# homeboard20.net
KiCad netlist of a schematic drawn in EAGLE
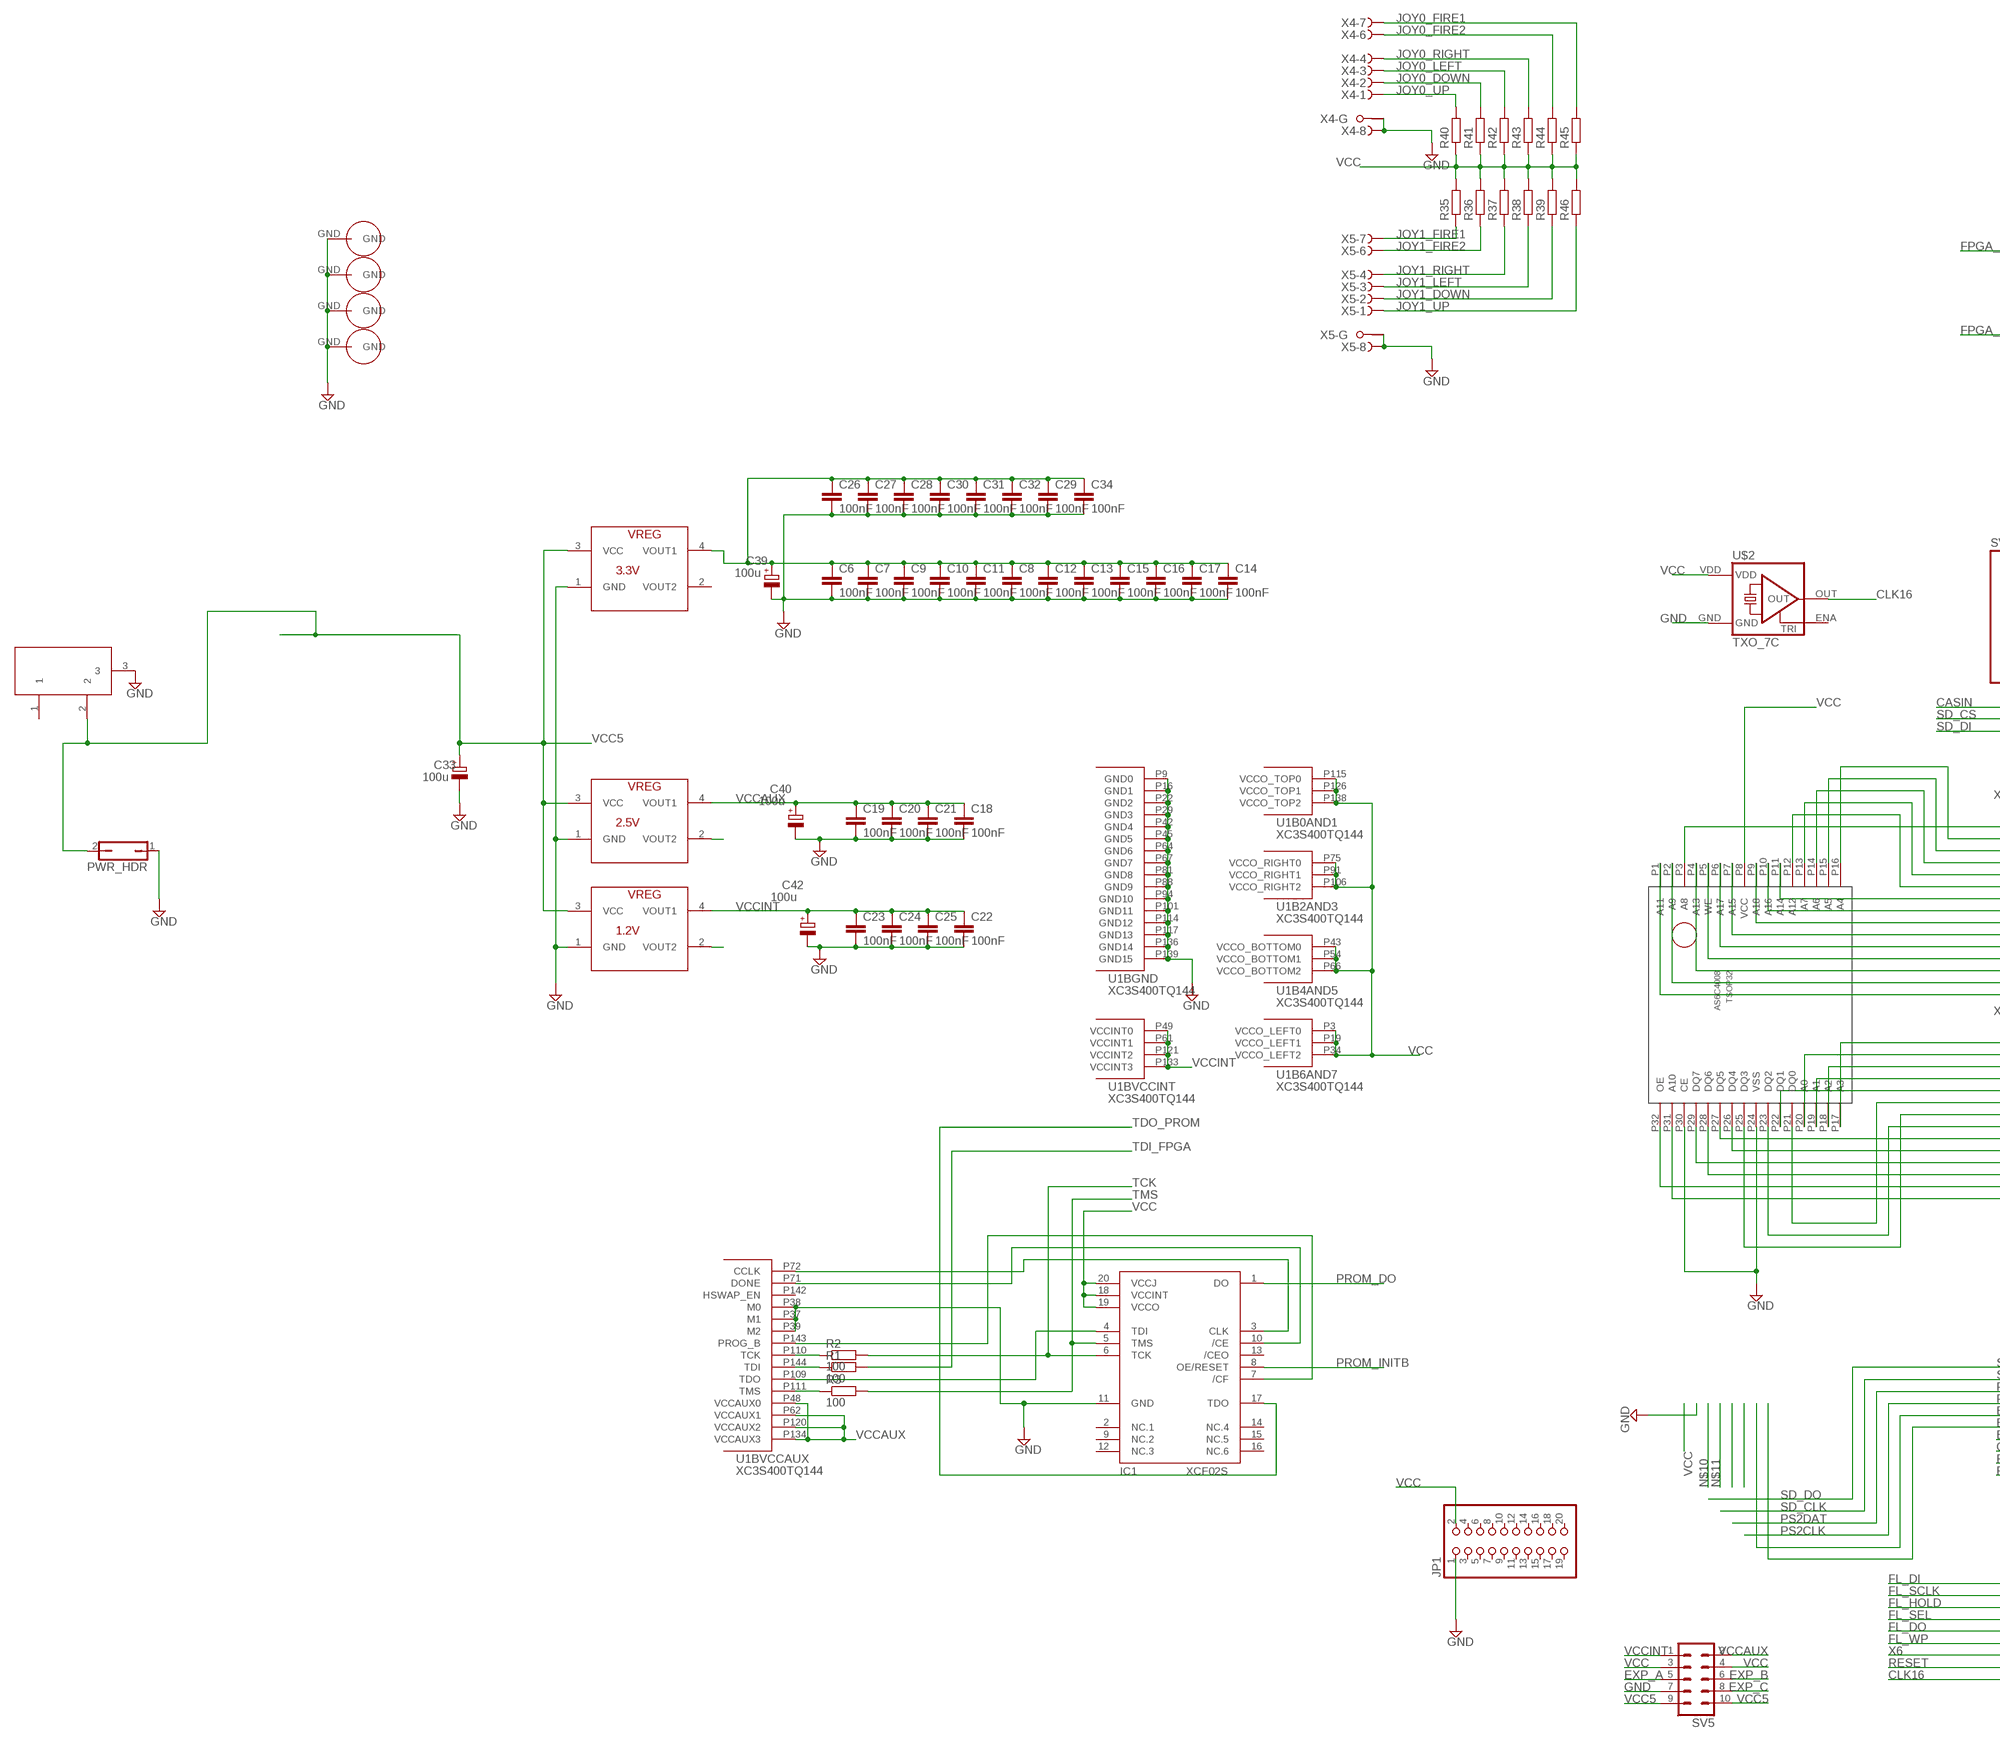
[diagram p0: schematic, sheet 1, part 1 of 3]
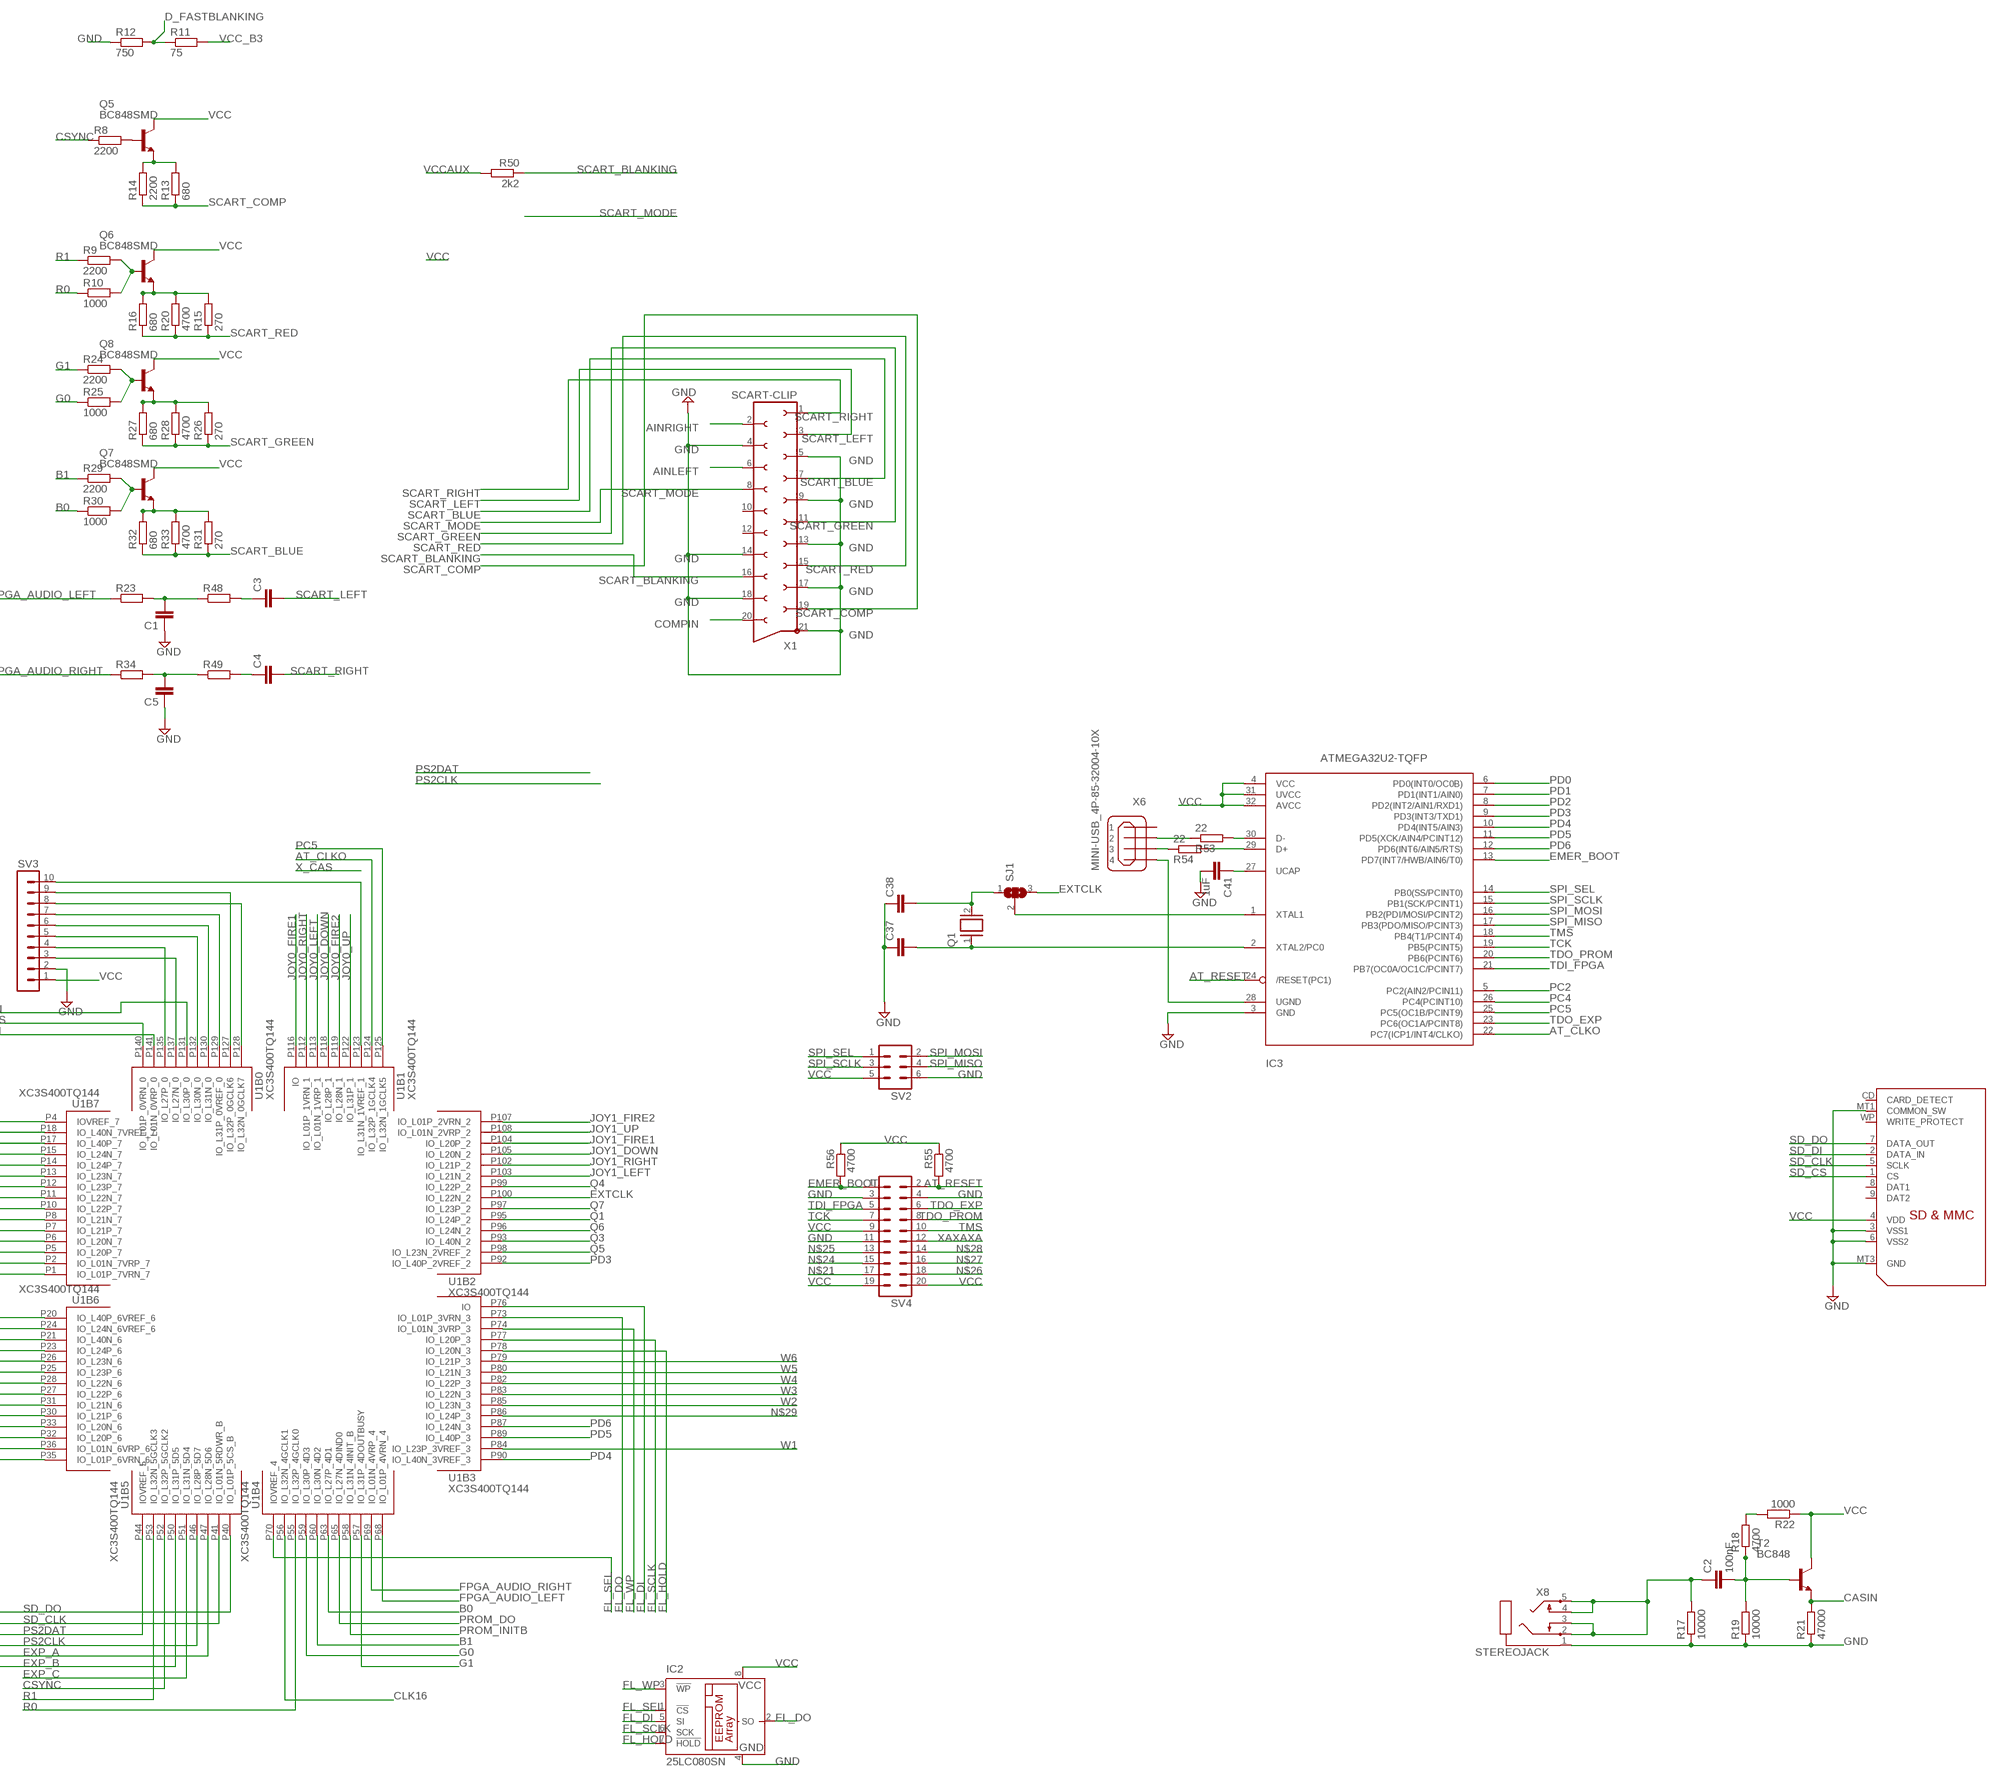
[diagram p1: schematic, sheet 1, part 2 of 3]
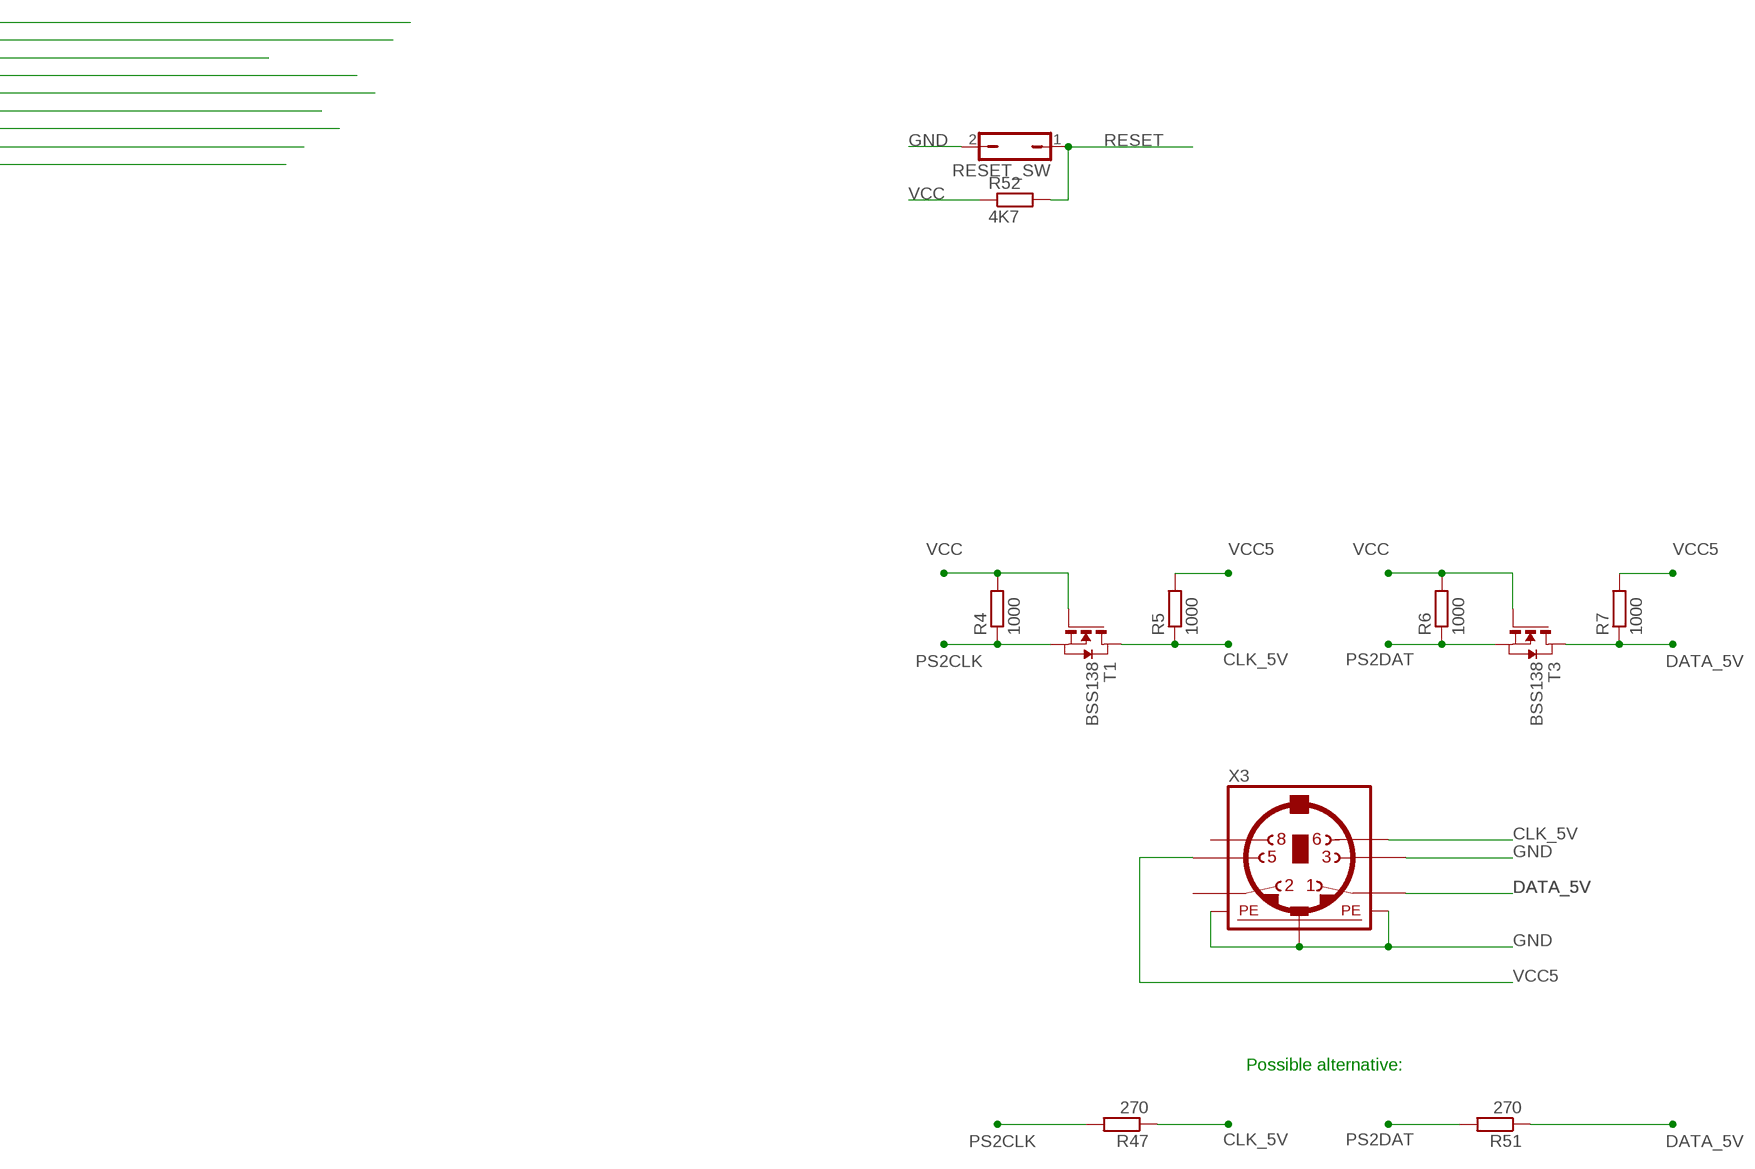
[diagram p2: schematic, sheet 1, part 3 of 3]

(export (version "E")
  (design (tool "Eeschema 10.0.6"))
  (components
    (comp (ref "C1")
      (value "C-EUC0603")
      (footprint "eagle-import:C0603")
      (libsource (lib "eagle-import") (part "resistor_C-EUC0603"))
    )
    (comp (ref "C2")
      (value "100nF")
      (footprint "eagle-import:C0603")
      (libsource (lib "eagle-import") (part "resistor_C-EUC0603"))
    )
    (comp (ref "C3")
      (value "C-EUC0603")
      (footprint "eagle-import:C0603")
      (libsource (lib "eagle-import") (part "resistor_C-EUC0603"))
    )
    (comp (ref "C4")
      (value "C-EUC0603")
      (footprint "eagle-import:C0603")
      (libsource (lib "eagle-import") (part "resistor_C-EUC0603"))
    )
    (comp (ref "C5")
      (value "C-EUC0603")
      (footprint "eagle-import:C0603")
      (libsource (lib "eagle-import") (part "resistor_C-EUC0603"))
    )
    (comp (ref "C6")
      (value "100nF")
      (footprint "eagle-import:C0603")
      (libsource (lib "eagle-import") (part "C-EUC0603"))
    )
    (comp (ref "C7")
      (value "100nF")
      (footprint "eagle-import:C0603")
      (libsource (lib "eagle-import") (part "C-EUC0603"))
    )
    (comp (ref "C8")
      (value "100nF")
      (footprint "eagle-import:C0603")
      (libsource (lib "eagle-import") (part "C-EUC0603"))
    )
    (comp (ref "C9")
      (value "100nF")
      (footprint "eagle-import:C0603")
      (libsource (lib "eagle-import") (part "C-EUC0603"))
    )
    (comp (ref "C10")
      (value "100nF")
      (footprint "eagle-import:C0603")
      (libsource (lib "eagle-import") (part "C-EUC0603"))
    )
    (comp (ref "C11")
      (value "100nF")
      (footprint "eagle-import:C0603")
      (libsource (lib "eagle-import") (part "C-EUC0603"))
    )
    (comp (ref "C12")
      (value "100nF")
      (footprint "eagle-import:C0603")
      (libsource (lib "eagle-import") (part "C-EUC0603"))
    )
    (comp (ref "C13")
      (value "100nF")
      (footprint "eagle-import:C0603")
      (libsource (lib "eagle-import") (part "C-EUC0603"))
    )
    (comp (ref "C14")
      (value "100nF")
      (footprint "eagle-import:C0603")
      (libsource (lib "eagle-import") (part "C-EUC0603"))
    )
    (comp (ref "C15")
      (value "100nF")
      (footprint "eagle-import:C0603")
      (libsource (lib "eagle-import") (part "C-EUC0603"))
    )
    (comp (ref "C16")
      (value "100nF")
      (footprint "eagle-import:C0603")
      (libsource (lib "eagle-import") (part "C-EUC0603"))
    )
    (comp (ref "C17")
      (value "100nF")
      (footprint "eagle-import:C0603")
      (libsource (lib "eagle-import") (part "C-EUC0603"))
    )
    (comp (ref "C18")
      (value "100nF")
      (footprint "eagle-import:C0603")
      (libsource (lib "eagle-import") (part "C-EUC0603"))
    )
    (comp (ref "C19")
      (value "100nF")
      (footprint "eagle-import:C0603")
      (libsource (lib "eagle-import") (part "C-EUC0603"))
    )
    (comp (ref "C20")
      (value "100nF")
      (footprint "eagle-import:C0603")
      (libsource (lib "eagle-import") (part "C-EUC0603"))
    )
    (comp (ref "C21")
      (value "100nF")
      (footprint "eagle-import:C0603")
      (libsource (lib "eagle-import") (part "C-EUC0603"))
    )
    (comp (ref "C22")
      (value "100nF")
      (footprint "eagle-import:C0603")
      (libsource (lib "eagle-import") (part "C-EUC0603"))
    )
    (comp (ref "C23")
      (value "100nF")
      (footprint "eagle-import:C0603")
      (libsource (lib "eagle-import") (part "C-EUC0603"))
    )
    (comp (ref "C24")
      (value "100nF")
      (footprint "eagle-import:C0603")
      (libsource (lib "eagle-import") (part "C-EUC0603"))
    )
    (comp (ref "C25")
      (value "100nF")
      (footprint "eagle-import:C0603")
      (libsource (lib "eagle-import") (part "C-EUC0603"))
    )
    (comp (ref "C26")
      (value "100nF")
      (footprint "eagle-import:C0603")
      (libsource (lib "eagle-import") (part "C-EUC0603"))
    )
    (comp (ref "C27")
      (value "100nF")
      (footprint "eagle-import:C0603")
      (libsource (lib "eagle-import") (part "C-EUC0603"))
    )
    (comp (ref "C28")
      (value "100nF")
      (footprint "eagle-import:C0603")
      (libsource (lib "eagle-import") (part "C-EUC0603"))
    )
    (comp (ref "C29")
      (value "100nF")
      (footprint "eagle-import:C0603")
      (libsource (lib "eagle-import") (part "C-EUC0603"))
    )
    (comp (ref "C30")
      (value "100nF")
      (footprint "eagle-import:C0603")
      (libsource (lib "eagle-import") (part "C-EUC0603"))
    )
    (comp (ref "C31")
      (value "100nF")
      (footprint "eagle-import:C0603")
      (libsource (lib "eagle-import") (part "C-EUC0603"))
    )
    (comp (ref "C32")
      (value "100nF")
      (footprint "eagle-import:C0603")
      (libsource (lib "eagle-import") (part "C-EUC0603"))
    )
    (comp (ref "C33")
      (value "100u")
      (footprint "eagle-import:PANASONIC_D")
      (libsource (lib "eagle-import") (part "CPOL-EUD"))
    )
    (comp (ref "C34")
      (value "100nF")
      (footprint "eagle-import:C0603")
      (libsource (lib "eagle-import") (part "C-EUC0603"))
    )
    (comp (ref "C37")
      (value "C-EUC0805")
      (footprint "eagle-import:C0805")
      (libsource (lib "eagle-import") (part "C-EUC0805"))
    )
    (comp (ref "C38")
      (value "C-EUC0805")
      (footprint "eagle-import:C0805")
      (libsource (lib "eagle-import") (part "C-EUC0805"))
    )
    (comp (ref "C39")
      (value "100u")
      (footprint "eagle-import:PANASONIC_D")
      (libsource (lib "eagle-import") (part "CPOL-EUD"))
    )
    (comp (ref "C40")
      (value "100u")
      (footprint "eagle-import:PANASONIC_D")
      (libsource (lib "eagle-import") (part "CPOL-EUD"))
    )
    (comp (ref "C41")
      (value "1uF")
      (footprint "eagle-import:C0805")
      (libsource (lib "eagle-import") (part "C-EUC0805"))
    )
    (comp (ref "C42")
      (value "100u")
      (footprint "eagle-import:PANASONIC_D")
      (libsource (lib "eagle-import") (part "CPOL-EUD"))
    )
    (comp (ref "IC1")
      (value "XCF02S")
      (footprint "eagle-import:VO20")
      (libsource (lib "eagle-import") (part "XCF02S"))
    )
    (comp (ref "IC2")
      (value "25LC080SN")
      (footprint "eagle-import:SO-08")
      (fields (field (name "MF") "MICROCHIP") (field (name "MPN") "25LC080/SN"))
      (libsource (lib "eagle-import") (part "25SNLC080"))
    )
    (comp (ref "IC3")
      (value "ATMEGA32U2-TQFP")
      (footprint "eagle-import:TQFP32-08")
      (libsource (lib "eagle-import") (part "ATMEGA32U2-TQFP"))
    )
    (comp (ref "JP1")
      (value "PINHD-2X10")
      (footprint "eagle-import:2X10")
      (libsource (lib "eagle-import") (part "PINHD-2X10"))
    )
    (comp (ref "PWR_HDR")
      (value "JP1Q")
      (footprint "eagle-import:JP1")
      (libsource (lib "eagle-import") (part "JP1Q"))
    )
    (comp (ref "Q1")
      (value "XTAL/S")
      (footprint "eagle-import:QS")
      (libsource (lib "eagle-import") (part "XTAL/S"))
    )
    (comp (ref "Q5")
      (value "BC848SMD")
      (footprint "eagle-import:SOT23")
      (libsource (lib "eagle-import") (part "BC848SMD"))
    )
    (comp (ref "Q6")
      (value "BC848SMD")
      (footprint "eagle-import:SOT23")
      (libsource (lib "eagle-import") (part "BC848SMD"))
    )
    (comp (ref "Q7")
      (value "BC848SMD")
      (footprint "eagle-import:SOT23")
      (libsource (lib "eagle-import") (part "BC848SMD"))
    )
    (comp (ref "Q8")
      (value "BC848SMD")
      (footprint "eagle-import:SOT23")
      (libsource (lib "eagle-import") (part "BC848SMD"))
    )
    (comp (ref "R1")
      (value "100")
      (footprint "eagle-import:R0805")
      (libsource (lib "eagle-import") (part "R-EU_R0805"))
    )
    (comp (ref "R2")
      (value "100")
      (footprint "eagle-import:R0805")
      (libsource (lib "eagle-import") (part "R-EU_R0805"))
    )
    (comp (ref "R3")
      (value "100")
      (footprint "eagle-import:R0805")
      (libsource (lib "eagle-import") (part "R-EU_R0805"))
    )
    (comp (ref "R4")
      (value "1000")
      (footprint "eagle-import:R0805")
      (libsource (lib "eagle-import") (part "R-EU_R0805"))
    )
    (comp (ref "R5")
      (value "1000")
      (footprint "eagle-import:R0805")
      (libsource (lib "eagle-import") (part "R-EU_R0805"))
    )
    (comp (ref "R6")
      (value "1000")
      (footprint "eagle-import:R0805")
      (libsource (lib "eagle-import") (part "R-EU_R0805"))
    )
    (comp (ref "R7")
      (value "1000")
      (footprint "eagle-import:R0805")
      (libsource (lib "eagle-import") (part "R-EU_R0805"))
    )
    (comp (ref "R8")
      (value "2200")
      (footprint "eagle-import:R0805")
      (libsource (lib "eagle-import") (part "R-EU_R0805"))
    )
    (comp (ref "R9")
      (value "2200")
      (footprint "eagle-import:R0805")
      (libsource (lib "eagle-import") (part "R-EU_R0805"))
    )
    (comp (ref "R10")
      (value "1000")
      (footprint "eagle-import:R0805")
      (libsource (lib "eagle-import") (part "R-EU_R0805"))
    )
    (comp (ref "R11")
      (value "75")
      (footprint "eagle-import:R0805")
      (libsource (lib "eagle-import") (part "R-EU_R0805"))
    )
    (comp (ref "R12")
      (value "750")
      (footprint "eagle-import:R0805")
      (libsource (lib "eagle-import") (part "R-EU_R0805"))
    )
    (comp (ref "R13")
      (value "680")
      (footprint "eagle-import:R0805")
      (libsource (lib "eagle-import") (part "R-EU_R0805"))
    )
    (comp (ref "R14")
      (value "2200")
      (footprint "eagle-import:R0805")
      (libsource (lib "eagle-import") (part "R-EU_R0805"))
    )
    (comp (ref "R15")
      (value "270")
      (footprint "eagle-import:R0805")
      (libsource (lib "eagle-import") (part "R-EU_R0805"))
    )
    (comp (ref "R16")
      (value "680")
      (footprint "eagle-import:R0805")
      (libsource (lib "eagle-import") (part "R-EU_R0805"))
    )
    (comp (ref "R17")
      (value "10000")
      (footprint "eagle-import:R0805")
      (libsource (lib "eagle-import") (part "R-EU_R0805"))
    )
    (comp (ref "R18")
      (value "4700")
      (footprint "eagle-import:R0805")
      (libsource (lib "eagle-import") (part "R-EU_R0805"))
    )
    (comp (ref "R19")
      (value "10000")
      (footprint "eagle-import:R0805")
      (libsource (lib "eagle-import") (part "R-EU_R0805"))
    )
    (comp (ref "R20")
      (value "4700")
      (footprint "eagle-import:R0805")
      (libsource (lib "eagle-import") (part "R-EU_R0805"))
    )
    (comp (ref "R21")
      (value "47000")
      (footprint "eagle-import:R0805")
      (libsource (lib "eagle-import") (part "R-EU_R0805"))
    )
    (comp (ref "R22")
      (value "1000")
      (footprint "eagle-import:R0805")
      (libsource (lib "eagle-import") (part "R-EU_R0805"))
    )
    (comp (ref "R23")
      (value "R-EU_M0805")
      (footprint "eagle-import:M0805")
      (libsource (lib "eagle-import") (part "resistor_R-EU_M0805"))
    )
    (comp (ref "R24")
      (value "2200")
      (footprint "eagle-import:R0805")
      (libsource (lib "eagle-import") (part "R-EU_R0805"))
    )
    (comp (ref "R25")
      (value "1000")
      (footprint "eagle-import:R0805")
      (libsource (lib "eagle-import") (part "R-EU_R0805"))
    )
    (comp (ref "R26")
      (value "270")
      (footprint "eagle-import:R0805")
      (libsource (lib "eagle-import") (part "R-EU_R0805"))
    )
    (comp (ref "R27")
      (value "680")
      (footprint "eagle-import:R0805")
      (libsource (lib "eagle-import") (part "R-EU_R0805"))
    )
    (comp (ref "R28")
      (value "4700")
      (footprint "eagle-import:R0805")
      (libsource (lib "eagle-import") (part "R-EU_R0805"))
    )
    (comp (ref "R29")
      (value "2200")
      (footprint "eagle-import:R0805")
      (libsource (lib "eagle-import") (part "R-EU_R0805"))
    )
    (comp (ref "R30")
      (value "1000")
      (footprint "eagle-import:R0805")
      (libsource (lib "eagle-import") (part "R-EU_R0805"))
    )
    (comp (ref "R31")
      (value "270")
      (footprint "eagle-import:R0805")
      (libsource (lib "eagle-import") (part "R-EU_R0805"))
    )
    (comp (ref "R32")
      (value "680")
      (footprint "eagle-import:R0805")
      (libsource (lib "eagle-import") (part "R-EU_R0805"))
    )
    (comp (ref "R33")
      (value "4700")
      (footprint "eagle-import:R0805")
      (libsource (lib "eagle-import") (part "R-EU_R0805"))
    )
    (comp (ref "R34")
      (value "R-EU_M0805")
      (footprint "eagle-import:M0805")
      (libsource (lib "eagle-import") (part "resistor_R-EU_M0805"))
    )
    (comp (ref "R35")
      (value "R-EU_M0805")
      (footprint "eagle-import:M0805")
      (libsource (lib "eagle-import") (part "resistor_R-EU_M0805"))
    )
    (comp (ref "R36")
      (value "R-EU_M0805")
      (footprint "eagle-import:M0805")
      (libsource (lib "eagle-import") (part "resistor_R-EU_M0805"))
    )
    (comp (ref "R37")
      (value "R-EU_M0805")
      (footprint "eagle-import:M0805")
      (libsource (lib "eagle-import") (part "resistor_R-EU_M0805"))
    )
    (comp (ref "R38")
      (value "R-EU_M0805")
      (footprint "eagle-import:M0805")
      (libsource (lib "eagle-import") (part "resistor_R-EU_M0805"))
    )
    (comp (ref "R39")
      (value "R-EU_M0805")
      (footprint "eagle-import:M0805")
      (libsource (lib "eagle-import") (part "resistor_R-EU_M0805"))
    )
    (comp (ref "R40")
      (value "R-EU_M0805")
      (footprint "eagle-import:M0805")
      (libsource (lib "eagle-import") (part "resistor_R-EU_M0805"))
    )
    (comp (ref "R41")
      (value "R-EU_M0805")
      (footprint "eagle-import:M0805")
      (libsource (lib "eagle-import") (part "resistor_R-EU_M0805"))
    )
    (comp (ref "R42")
      (value "R-EU_M0805")
      (footprint "eagle-import:M0805")
      (libsource (lib "eagle-import") (part "resistor_R-EU_M0805"))
    )
    (comp (ref "R43")
      (value "R-EU_M0805")
      (footprint "eagle-import:M0805")
      (libsource (lib "eagle-import") (part "resistor_R-EU_M0805"))
    )
    (comp (ref "R44")
      (value "R-EU_M0805")
      (footprint "eagle-import:M0805")
      (libsource (lib "eagle-import") (part "resistor_R-EU_M0805"))
    )
    (comp (ref "R45")
      (value "R-EU_M0805")
      (footprint "eagle-import:M0805")
      (libsource (lib "eagle-import") (part "resistor_R-EU_M0805"))
    )
    (comp (ref "R46")
      (value "R-EU_M0805")
      (footprint "eagle-import:M0805")
      (libsource (lib "eagle-import") (part "resistor_R-EU_M0805"))
    )
    (comp (ref "R47")
      (value "270")
      (footprint "eagle-import:R0805")
      (libsource (lib "eagle-import") (part "R-EU_R0805"))
    )
    (comp (ref "R48")
      (value "R-EU_M0805")
      (footprint "eagle-import:M0805")
      (libsource (lib "eagle-import") (part "resistor_R-EU_M0805"))
    )
    (comp (ref "R49")
      (value "R-EU_M0805")
      (footprint "eagle-import:M0805")
      (libsource (lib "eagle-import") (part "resistor_R-EU_M0805"))
    )
    (comp (ref "R50")
      (value "2k2")
      (footprint "eagle-import:M0805")
      (libsource (lib "eagle-import") (part "resistor_R-EU_M0805"))
    )
    (comp (ref "R51")
      (value "270")
      (footprint "eagle-import:R0805")
      (libsource (lib "eagle-import") (part "R-EU_R0805"))
    )
    (comp (ref "R52")
      (value "4K7")
      (footprint "eagle-import:M0805")
      (libsource (lib "eagle-import") (part "resistor_R-EU_M0805"))
    )
    (comp (ref "R53")
      (value "22")
      (footprint "eagle-import:R0805")
      (libsource (lib "eagle-import") (part "R-EU_R0805"))
    )
    (comp (ref "R54")
      (value "22")
      (footprint "eagle-import:R0805")
      (libsource (lib "eagle-import") (part "R-EU_R0805"))
    )
    (comp (ref "R55")
      (value "4700")
      (footprint "eagle-import:R0805")
      (libsource (lib "eagle-import") (part "R-EU_R0805"))
    )
    (comp (ref "R56")
      (value "4700")
      (footprint "eagle-import:R0805")
      (libsource (lib "eagle-import") (part "R-EU_R0805"))
    )
    (comp (ref "REG1.2")
      (value "1.2V")
      (footprint "eagle-import:SOT223")
      (libsource (lib "eagle-import") (part "NX1117"))
    )
    (comp (ref "REG2.5")
      (value "2.5V")
      (footprint "eagle-import:SOT223")
      (libsource (lib "eagle-import") (part "NX1117"))
    )
    (comp (ref "RESET_SW")
      (value "JP1Q")
      (footprint "eagle-import:JP1")
      (libsource (lib "eagle-import") (part "JP1Q"))
    )
    (comp (ref "SJ1")
      (value "SJ2W")
      (footprint "eagle-import:SJ_2")
      (libsource (lib "eagle-import") (part "SJ2W"))
    )
    (comp (ref "SV2")
      (value "MA03-2")
      (footprint "eagle-import:MA03-2")
      (libsource (lib "eagle-import") (part "MA03-2"))
    )
    (comp (ref "SV3")
      (value "MA10-1")
      (footprint "eagle-import:MA10-1")
      (libsource (lib "eagle-import") (part "MA10-1"))
    )
    (comp (ref "SV4")
      (value "MA10-2")
      (footprint "eagle-import:MA10-2")
      (libsource (lib "eagle-import") (part "MA10-2"))
    )
    (comp (ref "SV5")
      (value "MA05-2")
      (footprint "eagle-import:MA05-2")
      (libsource (lib "eagle-import") (part "MA05-2"))
    )
    (comp (ref "T1")
      (value "BSS138")
      (footprint "eagle-import:SOT-23")
      (libsource (lib "eagle-import") (part "NMOSSOT23"))
    )
    (comp (ref "T2")
      (value "BC848")
      (footprint "eagle-import:SOT23")
      (libsource (lib "eagle-import") (part "BC848"))
    )
    (comp (ref "T3")
      (value "BSS138")
      (footprint "eagle-import:SOT-23")
      (libsource (lib "eagle-import") (part "NMOSSOT23"))
    )
    (comp (ref "U$1")
      (value "GNDHOLE")
      (footprint "eagle-import:GNDHOLE")
      (libsource (lib "eagle-import") (part "GNDHOLE"))
    )
    (comp (ref "U$2")
      (value "TXO_7C")
      (footprint "eagle-import:OSC_7C")
      (libsource (lib "eagle-import") (part "TXO_7C"))
    )
    (comp (ref "U$3")
      (value "SDMMCNOHOLE")
      (footprint "eagle-import:SDCARD-NOHOLE")
      (libsource (lib "eagle-import") (part "SDMMCNOHOLE"))
    )
    (comp (ref "U$4")
      (value "3.3V")
      (footprint "eagle-import:SOT223")
      (libsource (lib "eagle-import") (part "NX1117"))
    )
    (comp (ref "U$6")
      (value "AS6C4008")
      (footprint "eagle-import:TSOP32")
      (libsource (lib "eagle-import") (part "AS6C4008"))
    )
    (comp (ref "U$7")
      (value "GNDHOLE")
      (footprint "eagle-import:GNDHOLE")
      (libsource (lib "eagle-import") (part "GNDHOLE"))
    )
    (comp (ref "U$8")
      (value "GNDHOLE")
      (footprint "eagle-import:GNDHOLE")
      (libsource (lib "eagle-import") (part "GNDHOLE"))
    )
    (comp (ref "U$9")
      (value "GNDHOLE")
      (footprint "eagle-import:GNDHOLE")
      (libsource (lib "eagle-import") (part "GNDHOLE"))
    )
    (comp (ref "U1")
      (value "XC3S400TQ144")
      (footprint "eagle-import:TQ144")
      (libsource (lib "eagle-import") (part "XC3S400TQ144"))
    )
    (comp (ref "X1")
      (value "SCART-CLIP")
      (footprint "eagle-import:SCART-CLIP")
      (libsource (lib "eagle-import") (part "SCART-CLIP"))
    )
    (comp (ref "X3")
      (value "MINI_DIN_6")
      (footprint "eagle-import:M_DIN6")
      (libsource (lib "eagle-import") (part "MINI_DIN_6"))
    )
    (comp (ref "X4")
      (value "F09HPS")
      (footprint "eagle-import:F09HP")
      (libsource (lib "eagle-import") (part "F09HPS"))
    )
    (comp (ref "X5")
      (value "F09HPS")
      (footprint "eagle-import:F09HP")
      (libsource (lib "eagle-import") (part "F09HPS"))
    )
    (comp (ref "X6")
      (value "MINI-USB_4P-85-32004-10X")
      (footprint "eagle-import:85-32004-10X")
      (libsource (lib "eagle-import") (part "MINI-USB_4P-85-32004-10X"))
    )
    (comp (ref "X7")
      (value "DC21MMX")
      (footprint "eagle-import:DC-21MM")
      (libsource (lib "eagle-import") (part "DC21MMX"))
    )
    (comp (ref "X8")
      (value "STEREOJACK")
      (footprint "eagle-import:20-0137")
      (libsource (lib "eagle-import") (part "STEREOJACK"))
    )
  )
  (nets
    (net (code "1") (name "/1") (class "Default")
      (node (ref "X7") (pin "1") (pinfunction "1_1") (pintype "power_in"))
    )
    (net (code "2") (name "/AINLEFT") (class "Default")
      (node (ref "X1") (pin "6") (pinfunction "6_6") (pintype "passive"))
    )
    (net (code "3") (name "/AINRIGHT") (class "Default")
      (node (ref "X1") (pin "2") (pinfunction "2_2") (pintype "passive"))
    )
    (net (code "4") (name "/AT_CLKO") (class "Default")
      (node (ref "IC3") (pin "22") (pinfunction "PC7(ICP1/INT4/CLKO)_22") (pintype "bidirectional"))
      (node (ref "U1") (pin "P124") (pinfunction "IO_L32P_1GCLK4_P124") (pintype "bidirectional"))
    )
    (net (code "5") (name "/AT_RESET") (class "Default")
      (node (ref "IC3") (pin "24") (pinfunction "/RESET(PC1)_24") (pintype "bidirectional"))
      (node (ref "R55") (pin "2") (pinfunction "2_2") (pintype "passive"))
      (node (ref "SV4") (pin "2") (pinfunction "2_2") (pintype "passive"))
    )
    (net (code "6") (name "/B0") (class "Default")
      (node (ref "R30") (pin "1") (pinfunction "1_1") (pintype "passive"))
      (node (ref "U1") (pin "P63") (pinfunction "IO_L27P_4D1_P63") (pintype "bidirectional"))
    )
    (net (code "7") (name "/B1") (class "Default")
      (node (ref "R29") (pin "1") (pinfunction "1_1") (pintype "passive"))
      (node (ref "U1") (pin "P60") (pinfunction "IO_L30N_4D2_P60") (pintype "bidirectional"))
    )
    (net (code "8") (name "/CASIN") (class "Default")
      (node (ref "R21") (pin "2") (pinfunction "2_2") (pintype "passive"))
      (node (ref "T2") (pin "2") (pinfunction "E_2") (pintype "passive"))
      (node (ref "U1") (pin "P131") (pinfunction "IO_L30P_0_P131") (pintype "bidirectional"))
    )
    (net (code "9") (name "/CLK16") (class "Default")
      (node (ref "U$2") (pin "OUT") (pinfunction "OUT_OUT") (pintype "output"))
      (node (ref "U1") (pin "P56") (pinfunction "IO_L32N_4GCLK1_P56") (pintype "bidirectional"))
    )
    (net (code "10") (name "/CLK_5V") (class "Default")
      (node (ref "R47") (pin "1") (pinfunction "1_1") (pintype "passive"))
      (node (ref "R5") (pin "1") (pinfunction "1_1") (pintype "passive"))
      (node (ref "T1") (pin "1") (pinfunction "D_1") (pintype "passive"))
      (node (ref "X3") (pin "6") (pinfunction "6_6") (pintype "passive"))
    )
    (net (code "11") (name "/COMPIN") (class "Default")
      (node (ref "X1") (pin "20") (pinfunction "20_20") (pintype "passive"))
    )
    (net (code "12") (name "/CSYNC") (class "Default")
      (node (ref "R8") (pin "1") (pinfunction "1_1") (pintype "passive"))
      (node (ref "U1") (pin "P52") (pinfunction "IO_L32P_5GCLK2_P52") (pintype "bidirectional"))
    )
    (net (code "13") (name "/DATA_5V") (class "Default")
      (node (ref "R51") (pin "1") (pinfunction "1_1") (pintype "passive"))
      (node (ref "R7") (pin "1") (pinfunction "1_1") (pintype "passive"))
      (node (ref "T3") (pin "1") (pinfunction "D_1") (pintype "passive"))
      (node (ref "X3") (pin "1") (pinfunction "1_1") (pintype "passive"))
    )
    (net (code "14") (name "/D_FASTBLANKING") (class "Default")
      (node (ref "R11") (pin "1") (pinfunction "1_1") (pintype "passive"))
      (node (ref "R12") (pin "2") (pinfunction "2_2") (pintype "passive"))
    )
    (net (code "15") (name "/EMER_BOOT") (class "Default")
      (node (ref "IC3") (pin "13") (pinfunction "PD7(INT7/HWB/AIN6/T0)_13") (pintype "bidirectional"))
      (node (ref "R56") (pin "2") (pinfunction "2_2") (pintype "passive"))
      (node (ref "SV4") (pin "1") (pinfunction "1_1") (pintype "passive"))
    )
    (net (code "16") (name "/EXP_A") (class "Default")
      (node (ref "SV5") (pin "5") (pinfunction "5_5") (pintype "passive"))
      (node (ref "U1") (pin "P47") (pinfunction "IO_L28N_5D6_P47") (pintype "bidirectional"))
    )
    (net (code "17") (name "/EXP_B") (class "Default")
      (node (ref "SV5") (pin "6") (pinfunction "6_6") (pintype "passive"))
      (node (ref "U1") (pin "P50") (pinfunction "IO_L31P_5D5_P50") (pintype "bidirectional"))
    )
    (net (code "18") (name "/EXP_C") (class "Default")
      (node (ref "SV5") (pin "8") (pinfunction "8_8") (pintype "passive"))
      (node (ref "U1") (pin "P51") (pinfunction "IO_L31N_5D4_P51") (pintype "bidirectional"))
    )
    (net (code "19") (name "/EXTCLK") (class "Default")
      (node (ref "SJ1") (pin "3") (pinfunction "3_3") (pintype "passive"))
      (node (ref "U1") (pin "P100") (pinfunction "IO_L22N_2_P100") (pintype "bidirectional"))
    )
    (net (code "20") (name "/FL_DI") (class "Default")
      (node (ref "IC2") (pin "5") (pinfunction "SI_5") (pintype "input"))
      (node (ref "U1") (pin "P76") (pinfunction "IO_P76") (pintype "bidirectional"))
    )
    (net (code "21") (name "/FL_DO") (class "Default")
      (node (ref "IC2") (pin "2") (pinfunction "SO_2") (pintype "bidirectional"))
      (node (ref "U1") (pin "P73") (pinfunction "IO_L01P_3VRN_3_P73") (pintype "bidirectional"))
    )
    (net (code "22") (name "/FL_HOLD") (class "Default")
      (node (ref "IC2") (pin "7") (pinfunction "~{HOLD}_7") (pintype "input"))
      (node (ref "U1") (pin "P78") (pinfunction "IO_L20N_3_P78") (pintype "bidirectional"))
    )
    (net (code "23") (name "/FL_SCLK") (class "Default")
      (node (ref "IC2") (pin "6") (pinfunction "SCK_6") (pintype "input"))
      (node (ref "U1") (pin "P77") (pinfunction "IO_L20P_3_P77") (pintype "bidirectional"))
    )
    (net (code "24") (name "/FL_SEL") (class "Default")
      (node (ref "IC2") (pin "1") (pinfunction "~{CS}_1") (pintype "input"))
      (node (ref "U1") (pin "P70") (pinfunction "IOVREF_4_P70") (pintype "bidirectional"))
    )
    (net (code "25") (name "/FL_WP") (class "Default")
      (node (ref "IC2") (pin "3") (pinfunction "~{WP}_3") (pintype "input"))
      (node (ref "U1") (pin "P74") (pinfunction "IO_L01N_3VRP_3_P74") (pintype "bidirectional"))
    )
    (net (code "26") (name "/FPGA_AUDIO_LEFT") (class "Default")
      (node (ref "R23") (pin "1") (pinfunction "1_1") (pintype "passive"))
      (node (ref "U1") (pin "P68") (pinfunction "IO_L01P_4VRN_4_P68") (pintype "bidirectional"))
    )
    (net (code "27") (name "/FPGA_AUDIO_RIGHT") (class "Default")
      (node (ref "R34") (pin "1") (pinfunction "1_1") (pintype "passive"))
      (node (ref "U1") (pin "P69") (pinfunction "IO_L01N_4VRP_4_P69") (pintype "bidirectional"))
    )
    (net (code "28") (name "/G0") (class "Default")
      (node (ref "R25") (pin "1") (pinfunction "1_1") (pintype "passive"))
      (node (ref "U1") (pin "P59") (pinfunction "IO_L30P_4D3_P59") (pintype "bidirectional"))
    )
    (net (code "29") (name "/G1") (class "Default")
      (node (ref "R24") (pin "1") (pinfunction "1_1") (pintype "passive"))
      (node (ref "U1") (pin "P57") (pinfunction "IO_L31P_4DOUTBUSY_P57") (pintype "bidirectional"))
    )
    (net (code "30") (name "/JOY0_DOWN") (class "Default")
      (node (ref "R41") (pin "2") (pinfunction "2_2") (pintype "passive"))
      (node (ref "U1") (pin "P118") (pinfunction "IO_L28P_1_P118") (pintype "bidirectional"))
      (node (ref "X4") (pin "2") (pinfunction "F_2") (pintype "passive"))
    )
    (net (code "31") (name "/JOY0_FIRE1") (class "Default")
      (node (ref "R45") (pin "2") (pinfunction "2_2") (pintype "passive"))
      (node (ref "U1") (pin "P116") (pinfunction "IO_P116") (pintype "bidirectional"))
      (node (ref "X4") (pin "7") (pinfunction "F_7") (pintype "passive"))
    )
    (net (code "32") (name "/JOY0_FIRE2") (class "Default")
      (node (ref "R44") (pin "2") (pinfunction "2_2") (pintype "passive"))
      (node (ref "U1") (pin "P119") (pinfunction "IO_L28N_1_P119") (pintype "bidirectional"))
      (node (ref "X4") (pin "6") (pinfunction "F_6") (pintype "passive"))
    )
    (net (code "33") (name "/JOY0_LEFT") (class "Default")
      (node (ref "R42") (pin "2") (pinfunction "2_2") (pintype "passive"))
      (node (ref "U1") (pin "P113") (pinfunction "IO_L01N_1VRP_1_P113") (pintype "bidirectional"))
      (node (ref "X4") (pin "3") (pinfunction "F_3") (pintype "passive"))
    )
    (net (code "34") (name "/JOY0_RIGHT") (class "Default")
      (node (ref "R43") (pin "2") (pinfunction "2_2") (pintype "passive"))
      (node (ref "U1") (pin "P112") (pinfunction "IO_L01P_1VRN_1_P112") (pintype "bidirectional"))
      (node (ref "X4") (pin "4") (pinfunction "F_4") (pintype "passive"))
    )
    (net (code "35") (name "/JOY0_UP") (class "Default")
      (node (ref "R40") (pin "2") (pinfunction "2_2") (pintype "passive"))
      (node (ref "U1") (pin "P122") (pinfunction "IO_L31P_1_P122") (pintype "bidirectional"))
      (node (ref "X4") (pin "1") (pinfunction "F_1") (pintype "passive"))
    )
    (net (code "36") (name "/JOY1_DOWN") (class "Default")
      (node (ref "R39") (pin "1") (pinfunction "1_1") (pintype "passive"))
      (node (ref "U1") (pin "P105") (pinfunction "IO_L20N_2_P105") (pintype "bidirectional"))
      (node (ref "X5") (pin "2") (pinfunction "F_2") (pintype "passive"))
    )
    (net (code "37") (name "/JOY1_FIRE1") (class "Default")
      (node (ref "R35") (pin "1") (pinfunction "1_1") (pintype "passive"))
      (node (ref "U1") (pin "P104") (pinfunction "IO_L20P_2_P104") (pintype "bidirectional"))
      (node (ref "X5") (pin "7") (pinfunction "F_7") (pintype "passive"))
    )
    (net (code "38") (name "/JOY1_FIRE2") (class "Default")
      (node (ref "R36") (pin "1") (pinfunction "1_1") (pintype "passive"))
      (node (ref "U1") (pin "P107") (pinfunction "IO_L01P_2VRN_2_P107") (pintype "bidirectional"))
      (node (ref "X5") (pin "6") (pinfunction "F_6") (pintype "passive"))
    )
    (net (code "39") (name "/JOY1_LEFT") (class "Default")
      (node (ref "R38") (pin "1") (pinfunction "1_1") (pintype "passive"))
      (node (ref "U1") (pin "P103") (pinfunction "IO_L21N_2_P103") (pintype "bidirectional"))
      (node (ref "X5") (pin "3") (pinfunction "F_3") (pintype "passive"))
    )
    (net (code "40") (name "/JOY1_RIGHT") (class "Default")
      (node (ref "R37") (pin "1") (pinfunction "1_1") (pintype "passive"))
      (node (ref "U1") (pin "P102") (pinfunction "IO_L21P_2_P102") (pintype "bidirectional"))
      (node (ref "X5") (pin "4") (pinfunction "F_4") (pintype "passive"))
    )
    (net (code "41") (name "/JOY1_UP") (class "Default")
      (node (ref "R46") (pin "1") (pinfunction "1_1") (pintype "passive"))
      (node (ref "U1") (pin "P108") (pinfunction "IO_L01N_2VRP_2_P108") (pintype "bidirectional"))
      (node (ref "X5") (pin "1") (pinfunction "F_1") (pintype "passive"))
    )
    (net (code "44") (name "/N$21") (class "Default")
      (node (ref "SV4") (pin "17") (pinfunction "17_17") (pintype "passive"))
    )
    (net (code "45") (name "/N$24") (class "Default")
      (node (ref "SV4") (pin "15") (pinfunction "15_15") (pintype "passive"))
    )
    (net (code "46") (name "/N$25") (class "Default")
      (node (ref "SV4") (pin "13") (pinfunction "13_13") (pintype "passive"))
    )
    (net (code "47") (name "/N$26") (class "Default")
      (node (ref "SV4") (pin "18") (pinfunction "18_18") (pintype "passive"))
    )
    (net (code "48") (name "/N$27") (class "Default")
      (node (ref "SV4") (pin "16") (pinfunction "16_16") (pintype "passive"))
    )
    (net (code "49") (name "/N$28") (class "Default")
      (node (ref "SV4") (pin "14") (pinfunction "14_14") (pintype "passive"))
    )
    (net (code "50") (name "/N$29") (class "Default")
      (node (ref "U1") (pin "P86") (pinfunction "IO_L24P_3_P86") (pintype "bidirectional"))
    )
    (net (code "51") (name "/PC2") (class "Default")
      (node (ref "IC3") (pin "5") (pinfunction "PC2(AIN2/PCIN11)_5") (pintype "bidirectional"))
    )
    (net (code "52") (name "/PC4") (class "Default")
      (node (ref "IC3") (pin "26") (pinfunction "PC4(PCINT10)_26") (pintype "bidirectional"))
    )
    (net (code "53") (name "/PC5") (class "Default")
      (node (ref "IC3") (pin "25") (pinfunction "PC5(OC1B/PCINT9)_25") (pintype "bidirectional"))
      (node (ref "U1") (pin "P125") (pinfunction "IO_L32N_1GCLK5_P125") (pintype "bidirectional"))
    )
    (net (code "54") (name "/PD0") (class "Default")
      (node (ref "IC3") (pin "6") (pinfunction "PD0(INT0/OC0B)_6") (pintype "bidirectional"))
    )
    (net (code "55") (name "/PD1") (class "Default")
      (node (ref "IC3") (pin "7") (pinfunction "PD1(INT1/AIN0)_7") (pintype "bidirectional"))
    )
    (net (code "56") (name "/PD2") (class "Default")
      (node (ref "IC3") (pin "8") (pinfunction "PD2(INT2/AIN1/RXD1)_8") (pintype "bidirectional"))
    )
    (net (code "57") (name "/PD3") (class "Default")
      (node (ref "IC3") (pin "9") (pinfunction "PD3(INT3/TXD1)_9") (pintype "bidirectional"))
      (node (ref "U1") (pin "P92") (pinfunction "IO_L40P_2VREF_2_P92") (pintype "bidirectional"))
    )
    (net (code "58") (name "/PD4") (class "Default")
      (node (ref "IC3") (pin "10") (pinfunction "PD4(INT5/AIN3)_10") (pintype "bidirectional"))
      (node (ref "U1") (pin "P90") (pinfunction "IO_L40N_3VREF_3_P90") (pintype "bidirectional"))
    )
    (net (code "59") (name "/PD5") (class "Default")
      (node (ref "IC3") (pin "11") (pinfunction "PD5(XCK/AIN4/PCINT12)_11") (pintype "bidirectional"))
      (node (ref "U1") (pin "P89") (pinfunction "IO_L40P_3_P89") (pintype "bidirectional"))
    )
    (net (code "60") (name "/PD6") (class "Default")
      (node (ref "IC3") (pin "12") (pinfunction "PD6(INT6/AIN5/RTS)_12") (pintype "bidirectional"))
      (node (ref "U1") (pin "P87") (pinfunction "IO_L24N_3_P87") (pintype "bidirectional"))
    )
    (net (code "61") (name "/PROM_DO") (class "Default")
      (node (ref "IC1") (pin "1") (pinfunction "DO_1") (pintype "bidirectional"))
      (node (ref "U1") (pin "P65") (pinfunction "IO_L27N_4DIND0_P65") (pintype "bidirectional"))
    )
    (net (code "62") (name "/PROM_INITB") (class "Default")
      (node (ref "IC1") (pin "8") (pinfunction "OE/RESET_8") (pintype "bidirectional"))
      (node (ref "U1") (pin "P58") (pinfunction "IO_L31N_4INIT_B_P58") (pintype "bidirectional"))
    )
    (net (code "63") (name "/PS2CLK") (class "Default")
      (node (ref "R4") (pin "1") (pinfunction "1_1") (pintype "passive"))
      (node (ref "R47") (pin "2") (pinfunction "2_2") (pintype "passive"))
      (node (ref "T1") (pin "2") (pinfunction "S_2") (pintype "passive"))
      (node (ref "U1") (pin "P46") (pinfunction "IO_L28P_5D7_P46") (pintype "bidirectional"))
    )
    (net (code "64") (name "/PS2DAT") (class "Default")
      (node (ref "R51") (pin "2") (pinfunction "2_2") (pintype "passive"))
      (node (ref "R6") (pin "1") (pinfunction "1_1") (pintype "passive"))
      (node (ref "T3") (pin "2") (pinfunction "S_2") (pintype "passive"))
      (node (ref "U1") (pin "P44") (pinfunction "IOVREF_5_P44") (pintype "bidirectional"))
    )
    (net (code "65") (name "/Q1") (class "Default")
      (node (ref "U1") (pin "P95") (pinfunction "IO_L24P_2_P95") (pintype "bidirectional"))
    )
    (net (code "66") (name "/Q3") (class "Default")
      (node (ref "U1") (pin "P93") (pinfunction "IO_L40N_2_P93") (pintype "bidirectional"))
    )
    (net (code "67") (name "/Q4") (class "Default")
      (node (ref "U1") (pin "P99") (pinfunction "IO_L22P_2_P99") (pintype "bidirectional"))
    )
    (net (code "68") (name "/Q5") (class "Default")
      (node (ref "U1") (pin "P98") (pinfunction "IO_L23N_2VREF_2_P98") (pintype "bidirectional"))
    )
    (net (code "69") (name "/Q6") (class "Default")
      (node (ref "U1") (pin "P96") (pinfunction "IO_L24N_2_P96") (pintype "bidirectional"))
    )
    (net (code "70") (name "/Q7") (class "Default")
      (node (ref "U1") (pin "P97") (pinfunction "IO_L23P_2_P97") (pintype "bidirectional"))
    )
    (net (code "71") (name "/R0") (class "Default")
      (node (ref "R10") (pin "1") (pinfunction "1_1") (pintype "passive"))
      (node (ref "U1") (pin "P55") (pinfunction "IO_L32P_4GCLK0_P55") (pintype "bidirectional"))
    )
    (net (code "72") (name "/R1") (class "Default")
      (node (ref "R9") (pin "1") (pinfunction "1_1") (pintype "passive"))
      (node (ref "U1") (pin "P53") (pinfunction "IO_L32N_5GCLK3_P53") (pintype "bidirectional"))
    )
    (net (code "73") (name "/RESET") (class "Default")
      (node (ref "R52") (pin "2") (pinfunction "2_2") (pintype "passive"))
      (node (ref "RESET_SW") (pin "1") (pinfunction "1_1") (pintype "passive"))
    )
    (net (code "74") (name "/SCART_BLANKING") (class "Default")
      (node (ref "R50") (pin "1") (pinfunction "1_1") (pintype "passive"))
      (node (ref "X1") (pin "16") (pinfunction "16_16") (pintype "passive"))
    )
    (net (code "75") (name "/SCART_BLUE") (class "Default")
      (node (ref "R31") (pin "1") (pinfunction "1_1") (pintype "passive"))
      (node (ref "R32") (pin "1") (pinfunction "1_1") (pintype "passive"))
      (node (ref "R33") (pin "1") (pinfunction "1_1") (pintype "passive"))
      (node (ref "X1") (pin "7") (pinfunction "7_7") (pintype "passive"))
    )
    (net (code "76") (name "/SCART_COMP") (class "Default")
      (node (ref "R13") (pin "1") (pinfunction "1_1") (pintype "passive"))
      (node (ref "R14") (pin "1") (pinfunction "1_1") (pintype "passive"))
      (node (ref "X1") (pin "19") (pinfunction "19_19") (pintype "passive"))
    )
    (net (code "77") (name "/SCART_GREEN") (class "Default")
      (node (ref "R26") (pin "1") (pinfunction "1_1") (pintype "passive"))
      (node (ref "R27") (pin "1") (pinfunction "1_1") (pintype "passive"))
      (node (ref "R28") (pin "1") (pinfunction "1_1") (pintype "passive"))
      (node (ref "X1") (pin "11") (pinfunction "11_11") (pintype "passive"))
    )
    (net (code "78") (name "/SCART_LEFT") (class "Default")
      (node (ref "C3") (pin "2") (pinfunction "2_2") (pintype "passive"))
      (node (ref "X1") (pin "3") (pinfunction "3_3") (pintype "passive"))
    )
    (net (code "79") (name "/SCART_MODE") (class "Default")
      (node (ref "X1") (pin "8") (pinfunction "8_8") (pintype "passive"))
    )
    (net (code "80") (name "/SCART_RED") (class "Default")
      (node (ref "R15") (pin "1") (pinfunction "1_1") (pintype "passive"))
      (node (ref "R16") (pin "1") (pinfunction "1_1") (pintype "passive"))
      (node (ref "R20") (pin "1") (pinfunction "1_1") (pintype "passive"))
      (node (ref "X1") (pin "15") (pinfunction "15_15") (pintype "passive"))
    )
    (net (code "81") (name "/SCART_RIGHT") (class "Default")
      (node (ref "C4") (pin "2") (pinfunction "2_2") (pintype "passive"))
      (node (ref "X1") (pin "1") (pinfunction "1_1") (pintype "passive"))
    )
    (net (code "82") (name "/SD_CLK") (class "Default")
      (node (ref "U$3") (pin "5") (pinfunction "SCLK_5") (pintype "input"))
      (node (ref "U1") (pin "P41") (pinfunction "IO_L01N_5RDWR_B_P41") (pintype "bidirectional"))
    )
    (net (code "83") (name "/SD_CS") (class "Default")
      (node (ref "U$3") (pin "1") (pinfunction "CS_1") (pintype "input"))
      (node (ref "U1") (pin "P140") (pinfunction "IO_L01P_0VRN_0_P140") (pintype "bidirectional"))
    )
    (net (code "84") (name "/SD_DI") (class "Default")
      (node (ref "U$3") (pin "2") (pinfunction "DATA_IN_2") (pintype "input"))
      (node (ref "U1") (pin "P141") (pinfunction "IO_L01N_0VRP_0_P141") (pintype "bidirectional"))
    )
    (net (code "85") (name "/SD_DO") (class "Default")
      (node (ref "U$3") (pin "7") (pinfunction "DATA_OUT_7") (pintype "output"))
      (node (ref "U1") (pin "P40") (pinfunction "IO_L01P_5CS_B_P40") (pintype "bidirectional"))
    )
    (net (code "86") (name "/SPI_MISO") (class "Default")
      (node (ref "IC3") (pin "17") (pinfunction "PB3(PDO/MISO/PCINT3)_17") (pintype "bidirectional"))
      (node (ref "SV2") (pin "4") (pinfunction "4_4") (pintype "passive"))
    )
    (net (code "87") (name "/SPI_MOSI") (class "Default")
      (node (ref "IC3") (pin "16") (pinfunction "PB2(PDI/MOSI/PCINT2)_16") (pintype "bidirectional"))
      (node (ref "SV2") (pin "2") (pinfunction "2_2") (pintype "passive"))
    )
    (net (code "88") (name "/SPI_SCLK") (class "Default")
      (node (ref "IC3") (pin "15") (pinfunction "PB1(SCK/PCINT1)_15") (pintype "bidirectional"))
      (node (ref "SV2") (pin "3") (pinfunction "3_3") (pintype "passive"))
    )
    (net (code "89") (name "/SPI_SEL") (class "Default")
      (node (ref "IC3") (pin "14") (pinfunction "PB0(SS/PCINT0)_14") (pintype "bidirectional"))
      (node (ref "SV2") (pin "1") (pinfunction "1_1") (pintype "passive"))
    )
    (net (code "90") (name "/TCK") (class "Default")
      (node (ref "IC1") (pin "6") (pinfunction "TCK_6") (pintype "bidirectional"))
      (node (ref "IC3") (pin "19") (pinfunction "PB5(PCINT5)_19") (pintype "bidirectional"))
      (node (ref "R2") (pin "2") (pinfunction "2_2") (pintype "passive"))
      (node (ref "SV4") (pin "7") (pinfunction "7_7") (pintype "passive"))
    )
    (net (code "91") (name "/TDI_FPGA") (class "Default")
      (node (ref "IC3") (pin "21") (pinfunction "PB7(OC0A/OC1C/PCINT7)_21") (pintype "bidirectional"))
      (node (ref "R1") (pin "2") (pinfunction "2_2") (pintype "passive"))
      (node (ref "SV4") (pin "5") (pinfunction "5_5") (pintype "passive"))
    )
    (net (code "92") (name "/TDO_EXP") (class "Default")
      (node (ref "IC3") (pin "23") (pinfunction "PC6(OC1A/PCINT8)_23") (pintype "bidirectional"))
      (node (ref "SV4") (pin "6") (pinfunction "6_6") (pintype "passive"))
    )
    (net (code "93") (name "/TDO_PROM") (class "Default")
      (node (ref "IC1") (pin "17") (pinfunction "TDO_17") (pintype "bidirectional"))
      (node (ref "IC3") (pin "20") (pinfunction "PB6(PCINT6)_20") (pintype "bidirectional"))
      (node (ref "SV4") (pin "8") (pinfunction "8_8") (pintype "passive"))
    )
    (net (code "94") (name "/TMS") (class "Default")
      (node (ref "IC1") (pin "5") (pinfunction "TMS_5") (pintype "bidirectional"))
      (node (ref "IC3") (pin "18") (pinfunction "PB4(T1/PCINT4)_18") (pintype "bidirectional"))
      (node (ref "R3") (pin "2") (pinfunction "2_2") (pintype "passive"))
      (node (ref "SV4") (pin "10") (pinfunction "10_10") (pintype "passive"))
    )
    (net (code "95") (name "/VCC") (class "Default")
      (node (ref "C10") (pin "1") (pinfunction "1_1") (pintype "passive"))
      (node (ref "C11") (pin "1") (pinfunction "1_1") (pintype "passive"))
      (node (ref "C12") (pin "1") (pinfunction "1_1") (pintype "passive"))
      (node (ref "C13") (pin "1") (pinfunction "1_1") (pintype "passive"))
      (node (ref "C14") (pin "1") (pinfunction "1_1") (pintype "passive"))
      (node (ref "C15") (pin "1") (pinfunction "1_1") (pintype "passive"))
      (node (ref "C16") (pin "1") (pinfunction "1_1") (pintype "passive"))
      (node (ref "C17") (pin "1") (pinfunction "1_1") (pintype "passive"))
      (node (ref "C26") (pin "1") (pinfunction "1_1") (pintype "passive"))
      (node (ref "C27") (pin "1") (pinfunction "1_1") (pintype "passive"))
      (node (ref "C28") (pin "1") (pinfunction "1_1") (pintype "passive"))
      (node (ref "C29") (pin "1") (pinfunction "1_1") (pintype "passive"))
      (node (ref "C30") (pin "1") (pinfunction "1_1") (pintype "passive"))
      (node (ref "C31") (pin "1") (pinfunction "1_1") (pintype "passive"))
      (node (ref "C32") (pin "1") (pinfunction "1_1") (pintype "passive"))
      (node (ref "C34") (pin "1") (pinfunction "1_1") (pintype "passive"))
      (node (ref "C39") (pin "+") (pinfunction "+_+") (pintype "passive"))
      (node (ref "C6") (pin "1") (pinfunction "1_1") (pintype "passive"))
      (node (ref "C7") (pin "1") (pinfunction "1_1") (pintype "passive"))
      (node (ref "C8") (pin "1") (pinfunction "1_1") (pintype "passive"))
      (node (ref "C9") (pin "1") (pinfunction "1_1") (pintype "passive"))
      (node (ref "IC1") (pin "18") (pinfunction "VCCINT_18") (pintype "bidirectional"))
      (node (ref "IC1") (pin "19") (pinfunction "VCCO_19") (pintype "bidirectional"))
      (node (ref "IC1") (pin "20") (pinfunction "VCCJ_20") (pintype "bidirectional"))
      (node (ref "IC2") (pin "8") (pinfunction "VCC_8") (pintype "power_in"))
      (node (ref "IC3") (pin "31") (pinfunction "UVCC_31") (pintype "bidirectional"))
      (node (ref "IC3") (pin "32") (pinfunction "AVCC_32") (pintype "bidirectional"))
      (node (ref "IC3") (pin "4") (pinfunction "VCC_4") (pintype "bidirectional"))
      (node (ref "JP1") (pin "2") (pinfunction "2_2") (pintype "passive"))
      (node (ref "Q5") (pin "3") (pinfunction "C_3") (pintype "passive"))
      (node (ref "Q6") (pin "3") (pinfunction "C_3") (pintype "passive"))
      (node (ref "Q7") (pin "3") (pinfunction "C_3") (pintype "passive"))
      (node (ref "Q8") (pin "3") (pinfunction "C_3") (pintype "passive"))
      (node (ref "R22") (pin "1") (pinfunction "1_1") (pintype "passive"))
      (node (ref "R35") (pin "2") (pinfunction "2_2") (pintype "passive"))
      (node (ref "R36") (pin "2") (pinfunction "2_2") (pintype "passive"))
      (node (ref "R37") (pin "2") (pinfunction "2_2") (pintype "passive"))
      (node (ref "R38") (pin "2") (pinfunction "2_2") (pintype "passive"))
      (node (ref "R39") (pin "2") (pinfunction "2_2") (pintype "passive"))
      (node (ref "R4") (pin "2") (pinfunction "2_2") (pintype "passive"))
      (node (ref "R40") (pin "1") (pinfunction "1_1") (pintype "passive"))
      (node (ref "R41") (pin "1") (pinfunction "1_1") (pintype "passive"))
      (node (ref "R42") (pin "1") (pinfunction "1_1") (pintype "passive"))
      (node (ref "R43") (pin "1") (pinfunction "1_1") (pintype "passive"))
      (node (ref "R44") (pin "1") (pinfunction "1_1") (pintype "passive"))
      (node (ref "R45") (pin "1") (pinfunction "1_1") (pintype "passive"))
      (node (ref "R46") (pin "2") (pinfunction "2_2") (pintype "passive"))
      (node (ref "R52") (pin "1") (pinfunction "1_1") (pintype "passive"))
      (node (ref "R55") (pin "1") (pinfunction "1_1") (pintype "passive"))
      (node (ref "R56") (pin "1") (pinfunction "1_1") (pintype "passive"))
      (node (ref "R6") (pin "2") (pinfunction "2_2") (pintype "passive"))
      (node (ref "SV2") (pin "5") (pinfunction "5_5") (pintype "passive"))
      (node (ref "SV3") (pin "1") (pinfunction "1_1") (pintype "passive"))
      (node (ref "SV4") (pin "19") (pinfunction "19_19") (pintype "passive"))
      (node (ref "SV4") (pin "20") (pinfunction "20_20") (pintype "passive"))
      (node (ref "SV4") (pin "9") (pinfunction "9_9") (pintype "passive"))
      (node (ref "SV5") (pin "3") (pinfunction "3_3") (pintype "passive"))
      (node (ref "SV5") (pin "4") (pinfunction "4_4") (pintype "passive"))
      (node (ref "T1") (pin "3") (pinfunction "G_3") (pintype "passive"))
      (node (ref "T2") (pin "3") (pinfunction "C_3") (pintype "passive"))
      (node (ref "T3") (pin "3") (pinfunction "G_3") (pintype "passive"))
      (node (ref "U$2") (pin "VDD") (pinfunction "VDD_VDD") (pintype "power_in"))
      (node (ref "U$3") (pin "4") (pinfunction "VDD_4") (pintype "power_in"))
      (node (ref "U$4") (pin "4") (pinfunction "VOUT1_4") (pintype "bidirectional"))
      (node (ref "U$6") (pin "P8") (pinfunction "VCC_P8") (pintype "bidirectional"))
      (node (ref "U1") (pin "P106") (pinfunction "VCCO_RIGHT2_P106") (pintype "passive"))
      (node (ref "U1") (pin "P115") (pinfunction "VCCO_TOP0_P115") (pintype "passive"))
      (node (ref "U1") (pin "P126") (pinfunction "VCCO_TOP1_P126") (pintype "passive"))
      (node (ref "U1") (pin "P138") (pinfunction "VCCO_TOP2_P138") (pintype "passive"))
      (node (ref "U1") (pin "P19") (pinfunction "VCCO_LEFT1_P19") (pintype "passive"))
      (node (ref "U1") (pin "P3") (pinfunction "VCCO_LEFT0_P3") (pintype "passive"))
      (node (ref "U1") (pin "P34") (pinfunction "VCCO_LEFT2_P34") (pintype "passive"))
      (node (ref "U1") (pin "P43") (pinfunction "VCCO_BOTTOM0_P43") (pintype "passive"))
      (node (ref "U1") (pin "P54") (pinfunction "VCCO_BOTTOM1_P54") (pintype "passive"))
      (node (ref "U1") (pin "P66") (pinfunction "VCCO_BOTTOM2_P66") (pintype "passive"))
      (node (ref "U1") (pin "P75") (pinfunction "VCCO_RIGHT0_P75") (pintype "passive"))
      (node (ref "U1") (pin "P91") (pinfunction "VCCO_RIGHT1_P91") (pintype "passive"))
    )
    (net (code "96") (name "/VCC5") (class "Default")
      (node (ref "C33") (pin "+") (pinfunction "+_+") (pintype "passive"))
      (node (ref "PWR_HDR") (pin "2") (pinfunction "2_2") (pintype "passive"))
      (node (ref "R5") (pin "2") (pinfunction "2_2") (pintype "passive"))
      (node (ref "R7") (pin "2") (pinfunction "2_2") (pintype "passive"))
      (node (ref "REG1.2") (pin "3") (pinfunction "VCC_3") (pintype "bidirectional"))
      (node (ref "REG2.5") (pin "3") (pinfunction "VCC_3") (pintype "bidirectional"))
      (node (ref "SV5") (pin "10") (pinfunction "10_10") (pintype "passive"))
      (node (ref "SV5") (pin "9") (pinfunction "9_9") (pintype "passive"))
      (node (ref "U$4") (pin "3") (pinfunction "VCC_3") (pintype "bidirectional"))
      (node (ref "X3") (pin "5") (pinfunction "5_5") (pintype "passive"))
      (node (ref "X7") (pin "2") (pinfunction "2_2") (pintype "power_in"))
    )
    (net (code "97") (name "/VCCAUX") (class "Default")
      (node (ref "C18") (pin "1") (pinfunction "1_1") (pintype "passive"))
      (node (ref "C19") (pin "1") (pinfunction "1_1") (pintype "passive"))
      (node (ref "C20") (pin "1") (pinfunction "1_1") (pintype "passive"))
      (node (ref "C21") (pin "1") (pinfunction "1_1") (pintype "passive"))
      (node (ref "C40") (pin "+") (pinfunction "+_+") (pintype "passive"))
      (node (ref "R50") (pin "2") (pinfunction "2_2") (pintype "passive"))
      (node (ref "REG2.5") (pin "4") (pinfunction "VOUT1_4") (pintype "bidirectional"))
      (node (ref "SV5") (pin "2") (pinfunction "2_2") (pintype "passive"))
      (node (ref "U1") (pin "P120") (pinfunction "VCCAUX2_P120") (pintype "passive"))
      (node (ref "U1") (pin "P134") (pinfunction "VCCAUX3_P134") (pintype "passive"))
      (node (ref "U1") (pin "P48") (pinfunction "VCCAUX0_P48") (pintype "passive"))
      (node (ref "U1") (pin "P62") (pinfunction "VCCAUX1_P62") (pintype "passive"))
    )
    (net (code "98") (name "/VCCINT") (class "Default")
      (node (ref "C22") (pin "1") (pinfunction "1_1") (pintype "passive"))
      (node (ref "C23") (pin "1") (pinfunction "1_1") (pintype "passive"))
      (node (ref "C24") (pin "1") (pinfunction "1_1") (pintype "passive"))
      (node (ref "C25") (pin "1") (pinfunction "1_1") (pintype "passive"))
      (node (ref "C42") (pin "+") (pinfunction "+_+") (pintype "passive"))
      (node (ref "REG1.2") (pin "4") (pinfunction "VOUT1_4") (pintype "bidirectional"))
      (node (ref "SV5") (pin "1") (pinfunction "1_1") (pintype "passive"))
      (node (ref "U1") (pin "P121") (pinfunction "VCCINT2_P121") (pintype "passive"))
      (node (ref "U1") (pin "P133") (pinfunction "VCCINT3_P133") (pintype "passive"))
      (node (ref "U1") (pin "P49") (pinfunction "VCCINT0_P49") (pintype "passive"))
      (node (ref "U1") (pin "P61") (pinfunction "VCCINT1_P61") (pintype "passive"))
    )
    (net (code "99") (name "/VCC_B3") (class "Default")
      (node (ref "R11") (pin "2") (pinfunction "2_2") (pintype "passive"))
    )
    (net (code "100") (name "/W1") (class "Default")
      (node (ref "U1") (pin "P84") (pinfunction "IO_L23P_3VREF_3_P84") (pintype "bidirectional"))
    )
    (net (code "101") (name "/W2") (class "Default")
      (node (ref "U1") (pin "P85") (pinfunction "IO_L23N_3_P85") (pintype "bidirectional"))
    )
    (net (code "102") (name "/W3") (class "Default")
      (node (ref "U1") (pin "P83") (pinfunction "IO_L22N_3_P83") (pintype "bidirectional"))
    )
    (net (code "103") (name "/W4") (class "Default")
      (node (ref "U1") (pin "P82") (pinfunction "IO_L22P_3_P82") (pintype "bidirectional"))
    )
    (net (code "104") (name "/W5") (class "Default")
      (node (ref "U1") (pin "P80") (pinfunction "IO_L21N_3_P80") (pintype "bidirectional"))
    )
    (net (code "105") (name "/W6") (class "Default")
      (node (ref "U1") (pin "P79") (pinfunction "IO_L21P_3_P79") (pintype "bidirectional"))
    )
    (net (code "107") (name "/XAXAXA") (class "Default")
      (node (ref "SV4") (pin "12") (pinfunction "12_12") (pintype "passive"))
    )
    (net (code "109") (name "GND") (class "Default")
      (node (ref "C1") (pin "1") (pinfunction "1_1") (pintype "passive"))
      (node (ref "C10") (pin "2") (pinfunction "2_2") (pintype "passive"))
      (node (ref "C11") (pin "2") (pinfunction "2_2") (pintype "passive"))
      (node (ref "C12") (pin "2") (pinfunction "2_2") (pintype "passive"))
      (node (ref "C13") (pin "2") (pinfunction "2_2") (pintype "passive"))
      (node (ref "C14") (pin "2") (pinfunction "2_2") (pintype "passive"))
      (node (ref "C15") (pin "2") (pinfunction "2_2") (pintype "passive"))
      (node (ref "C16") (pin "2") (pinfunction "2_2") (pintype "passive"))
      (node (ref "C17") (pin "2") (pinfunction "2_2") (pintype "passive"))
      (node (ref "C18") (pin "2") (pinfunction "2_2") (pintype "passive"))
      (node (ref "C19") (pin "2") (pinfunction "2_2") (pintype "passive"))
      (node (ref "C20") (pin "2") (pinfunction "2_2") (pintype "passive"))
      (node (ref "C21") (pin "2") (pinfunction "2_2") (pintype "passive"))
      (node (ref "C22") (pin "2") (pinfunction "2_2") (pintype "passive"))
      (node (ref "C23") (pin "2") (pinfunction "2_2") (pintype "passive"))
      (node (ref "C24") (pin "2") (pinfunction "2_2") (pintype "passive"))
      (node (ref "C25") (pin "2") (pinfunction "2_2") (pintype "passive"))
      (node (ref "C26") (pin "2") (pinfunction "2_2") (pintype "passive"))
      (node (ref "C27") (pin "2") (pinfunction "2_2") (pintype "passive"))
      (node (ref "C28") (pin "2") (pinfunction "2_2") (pintype "passive"))
      (node (ref "C29") (pin "2") (pinfunction "2_2") (pintype "passive"))
      (node (ref "C30") (pin "2") (pinfunction "2_2") (pintype "passive"))
      (node (ref "C31") (pin "2") (pinfunction "2_2") (pintype "passive"))
      (node (ref "C32") (pin "2") (pinfunction "2_2") (pintype "passive"))
      (node (ref "C33") (pin "-") (pinfunction "-_-") (pintype "passive"))
      (node (ref "C34") (pin "2") (pinfunction "2_2") (pintype "passive"))
      (node (ref "C37") (pin "1") (pinfunction "1_1") (pintype "passive"))
      (node (ref "C38") (pin "1") (pinfunction "1_1") (pintype "passive"))
      (node (ref "C39") (pin "-") (pinfunction "-_-") (pintype "passive"))
      (node (ref "C40") (pin "-") (pinfunction "-_-") (pintype "passive"))
      (node (ref "C41") (pin "2") (pinfunction "2_2") (pintype "passive"))
      (node (ref "C42") (pin "-") (pinfunction "-_-") (pintype "passive"))
      (node (ref "C5") (pin "1") (pinfunction "1_1") (pintype "passive"))
      (node (ref "C6") (pin "2") (pinfunction "2_2") (pintype "passive"))
      (node (ref "C7") (pin "2") (pinfunction "2_2") (pintype "passive"))
      (node (ref "C8") (pin "2") (pinfunction "2_2") (pintype "passive"))
      (node (ref "C9") (pin "2") (pinfunction "2_2") (pintype "passive"))
      (node (ref "IC1") (pin "11") (pinfunction "GND_11") (pintype "bidirectional"))
      (node (ref "IC2") (pin "4") (pinfunction "GND_4") (pintype "power_in"))
      (node (ref "IC3") (pin "3") (pinfunction "GND_3") (pintype "bidirectional"))
      (node (ref "JP1") (pin "1") (pinfunction "1_1") (pintype "passive"))
      (node (ref "PWR_HDR") (pin "1") (pinfunction "1_1") (pintype "passive"))
      (node (ref "R12") (pin "1") (pinfunction "1_1") (pintype "passive"))
      (node (ref "R17") (pin "1") (pinfunction "1_1") (pintype "passive"))
      (node (ref "R19") (pin "1") (pinfunction "1_1") (pintype "passive"))
      (node (ref "R21") (pin "1") (pinfunction "1_1") (pintype "passive"))
      (node (ref "REG1.2") (pin "1") (pinfunction "GND_1") (pintype "bidirectional"))
      (node (ref "REG2.5") (pin "1") (pinfunction "GND_1") (pintype "bidirectional"))
      (node (ref "RESET_SW") (pin "2") (pinfunction "2_2") (pintype "passive"))
      (node (ref "SV2") (pin "6") (pinfunction "6_6") (pintype "passive"))
      (node (ref "SV3") (pin "2") (pinfunction "2_2") (pintype "passive"))
      (node (ref "SV4") (pin "11") (pinfunction "11_11") (pintype "passive"))
      (node (ref "SV4") (pin "3") (pinfunction "3_3") (pintype "passive"))
      (node (ref "SV4") (pin "4") (pinfunction "4_4") (pintype "passive"))
      (node (ref "SV5") (pin "7") (pinfunction "7_7") (pintype "passive"))
      (node (ref "U$1") (pin "GND") (pinfunction "GND_GND") (pintype "bidirectional"))
      (node (ref "U$2") (pin "GND") (pinfunction "GND_GND") (pintype "power_in"))
      (node (ref "U$3") (pin "3") (pinfunction "VSS1_3") (pintype "power_in"))
      (node (ref "U$3") (pin "6") (pinfunction "VSS2_6") (pintype "power_in"))
      (node (ref "U$3") (pin "MT1") (pinfunction "COMMON_SW_MT1") (pintype "passive"))
      (node (ref "U$3") (pin "MT3") (pinfunction "GND_MT3") (pintype "power_in"))
      (node (ref "U$4") (pin "1") (pinfunction "GND_1") (pintype "bidirectional"))
      (node (ref "U$6") (pin "P24") (pinfunction "VSS_P24") (pintype "bidirectional"))
      (node (ref "U$6") (pin "P30") (pinfunction "CE_P30") (pintype "bidirectional"))
      (node (ref "U$7") (pin "GND") (pinfunction "GND_GND") (pintype "bidirectional"))
      (node (ref "U$8") (pin "GND") (pinfunction "GND_GND") (pintype "bidirectional"))
      (node (ref "U$9") (pin "GND") (pinfunction "GND_GND") (pintype "bidirectional"))
      (node (ref "U1") (pin "P101") (pinfunction "GND11_P101") (pintype "passive"))
      (node (ref "U1") (pin "P114") (pinfunction "GND12_P114") (pintype "passive"))
      (node (ref "U1") (pin "P117") (pinfunction "GND13_P117") (pintype "passive"))
      (node (ref "U1") (pin "P136") (pinfunction "GND14_P136") (pintype "passive"))
      (node (ref "U1") (pin "P139") (pinfunction "GND15_P139") (pintype "passive"))
      (node (ref "U1") (pin "P16") (pinfunction "GND1_P16") (pintype "passive"))
      (node (ref "U1") (pin "P22") (pinfunction "GND2_P22") (pintype "passive"))
      (node (ref "U1") (pin "P29") (pinfunction "GND3_P29") (pintype "passive"))
      (node (ref "U1") (pin "P37") (pinfunction "M1_P37") (pintype "bidirectional"))
      (node (ref "U1") (pin "P38") (pinfunction "M0_P38") (pintype "bidirectional"))
      (node (ref "U1") (pin "P39") (pinfunction "M2_P39") (pintype "bidirectional"))
      (node (ref "U1") (pin "P42") (pinfunction "GND4_P42") (pintype "passive"))
      (node (ref "U1") (pin "P45") (pinfunction "GND5_P45") (pintype "passive"))
      (node (ref "U1") (pin "P64") (pinfunction "GND6_P64") (pintype "passive"))
      (node (ref "U1") (pin "P67") (pinfunction "GND7_P67") (pintype "passive"))
      (node (ref "U1") (pin "P81") (pinfunction "GND8_P81") (pintype "passive"))
      (node (ref "U1") (pin "P88") (pinfunction "GND9_P88") (pintype "passive"))
      (node (ref "U1") (pin "P9") (pinfunction "GND0_P9") (pintype "passive"))
      (node (ref "U1") (pin "P94") (pinfunction "GND10_P94") (pintype "passive"))
      (node (ref "X1") (pin "13") (pinfunction "13_13") (pintype "passive"))
      (node (ref "X1") (pin "14") (pinfunction "14_14") (pintype "passive"))
      (node (ref "X1") (pin "17") (pinfunction "17_17") (pintype "passive"))
      (node (ref "X1") (pin "18") (pinfunction "18_18") (pintype "passive"))
      (node (ref "X1") (pin "21") (pinfunction "21_21") (pintype "passive"))
      (node (ref "X1") (pin "4") (pinfunction "4_4") (pintype "passive"))
      (node (ref "X1") (pin "5") (pinfunction "5_5") (pintype "passive"))
      (node (ref "X1") (pin "9") (pinfunction "9_9") (pintype "passive"))
      (node (ref "X3") (pin "3") (pinfunction "3_3") (pintype "passive"))
      (node (ref "X3") (pin "SH1") (pinfunction "PE1_SH1") (pintype "power_in"))
      (node (ref "X3") (pin "SH2") (pinfunction "PE2_SH2") (pintype "power_in"))
      (node (ref "X3") (pin "SH3") (pinfunction "PE3_SH3") (pintype "power_in"))
      (node (ref "X4") (pin "8") (pinfunction "F_8") (pintype "passive"))
      (node (ref "X4") (pin "G1") (pinfunction "G1_G1") (pintype "passive"))
      (node (ref "X5") (pin "8") (pinfunction "F_8") (pintype "passive"))
      (node (ref "X5") (pin "G1") (pinfunction "G1_G1") (pintype "passive"))
      (node (ref "X7") (pin "3") (pinfunction "3_3") (pintype "power_in"))
      (node (ref "X8") (pin "1") (pinfunction "1_1") (pintype "passive"))
    )
    (net (code "110") (name "Net-(C1-Pad2)") (class "Default")
      (node (ref "C1") (pin "2") (pinfunction "2_2") (pintype "passive"))
      (node (ref "R23") (pin "2") (pinfunction "2_2") (pintype "passive"))
      (node (ref "R48") (pin "1") (pinfunction "1_1") (pintype "passive"))
    )
    (net (code "111") (name "Net-(C2-Pad1)") (class "Default")
      (node (ref "C2") (pin "1") (pinfunction "1_1") (pintype "passive"))
      (node (ref "R17") (pin "2") (pinfunction "2_2") (pintype "passive"))
      (node (ref "X8") (pin "2") (pinfunction "2_2") (pintype "passive"))
      (node (ref "X8") (pin "3") (pinfunction "3_3") (pintype "passive"))
      (node (ref "X8") (pin "4") (pinfunction "4_4") (pintype "passive"))
      (node (ref "X8") (pin "5") (pinfunction "5_5") (pintype "passive"))
    )
    (net (code "112") (name "Net-(C3-Pad1)") (class "Default")
      (node (ref "C3") (pin "1") (pinfunction "1_1") (pintype "passive"))
      (node (ref "R48") (pin "2") (pinfunction "2_2") (pintype "passive"))
    )
    (net (code "113") (name "Net-(C4-Pad1)") (class "Default")
      (node (ref "C4") (pin "1") (pinfunction "1_1") (pintype "passive"))
      (node (ref "R49") (pin "2") (pinfunction "2_2") (pintype "passive"))
    )
    (net (code "114") (name "Net-(C5-Pad2)") (class "Default")
      (node (ref "C5") (pin "2") (pinfunction "2_2") (pintype "passive"))
      (node (ref "R34") (pin "2") (pinfunction "2_2") (pintype "passive"))
      (node (ref "R49") (pin "1") (pinfunction "1_1") (pintype "passive"))
    )
    (net (code "115") (name "Net-(C38-Pad2)") (class "Default")
      (node (ref "C38") (pin "2") (pinfunction "2_2") (pintype "passive"))
      (node (ref "Q1") (pin "2") (pinfunction "2_2") (pintype "passive"))
      (node (ref "SJ1") (pin "1") (pinfunction "1_1") (pintype "passive"))
    )
    (net (code "116") (name "Net-(IC1-CLK)") (class "Default")
      (node (ref "IC1") (pin "3") (pinfunction "CLK_3") (pintype "bidirectional"))
      (node (ref "U1") (pin "P72") (pinfunction "CCLK_P72") (pintype "bidirectional"))
    )
    (net (code "117") (name "Net-(IC1-TDI)") (class "Default")
      (node (ref "IC1") (pin "4") (pinfunction "TDI_4") (pintype "bidirectional"))
      (node (ref "U1") (pin "P109") (pinfunction "TDO_P109") (pintype "bidirectional"))
    )
    (net (code "118") (name "Net-(IC1-{slash}CE)") (class "Default")
      (node (ref "IC1") (pin "10") (pinfunction "/CE_10") (pintype "bidirectional"))
      (node (ref "U1") (pin "P71") (pinfunction "DONE_P71") (pintype "bidirectional"))
    )
    (net (code "119") (name "Net-(IC1-{slash}CF)") (class "Default")
      (node (ref "IC1") (pin "7") (pinfunction "/CF_7") (pintype "bidirectional"))
      (node (ref "U1") (pin "P143") (pinfunction "PROG_B_P143") (pintype "bidirectional"))
    )
    (net (code "120") (name "Net-(IC3-D+)") (class "Default")
      (node (ref "IC3") (pin "29") (pinfunction "D+_29") (pintype "bidirectional"))
      (node (ref "R54") (pin "2") (pinfunction "2_2") (pintype "passive"))
    )
    (net (code "121") (name "Net-(IC3-D-)") (class "Default")
      (node (ref "IC3") (pin "30") (pinfunction "D-_30") (pintype "bidirectional"))
      (node (ref "R53") (pin "2") (pinfunction "2_2") (pintype "passive"))
    )
    (net (code "122") (name "Net-(IC3-UCAP)") (class "Default")
      (node (ref "C41") (pin "1") (pinfunction "1_1") (pintype "passive"))
      (node (ref "IC3") (pin "27") (pinfunction "UCAP_27") (pintype "bidirectional"))
    )
    (net (code "123") (name "Net-(IC3-UGND)") (class "Default")
      (node (ref "IC3") (pin "28") (pinfunction "UGND_28") (pintype "bidirectional"))
      (node (ref "X6") (pin "4") (pinfunction "4_4") (pintype "passive"))
    )
    (net (code "124") (name "Net-(IC3-XTAL1)") (class "Default")
      (node (ref "IC3") (pin "1") (pinfunction "XTAL1_1") (pintype "bidirectional"))
      (node (ref "SJ1") (pin "2") (pinfunction "2_2") (pintype "passive"))
    )
    (net (code "125") (name "Net-(IC3-XTAL2{slash}PC0)") (class "Default")
      (node (ref "C37") (pin "2") (pinfunction "2_2") (pintype "passive"))
      (node (ref "IC3") (pin "2") (pinfunction "XTAL2/PC0_2") (pintype "bidirectional"))
      (node (ref "Q1") (pin "1") (pinfunction "1_1") (pintype "passive"))
    )
    (net (code "126") (name "Net-(Q5-B)") (class "Default")
      (node (ref "Q5") (pin "1") (pinfunction "B_1") (pintype "passive"))
      (node (ref "R8") (pin "2") (pinfunction "2_2") (pintype "passive"))
    )
    (net (code "127") (name "Net-(Q5-E)") (class "Default")
      (node (ref "Q5") (pin "2") (pinfunction "E_2") (pintype "passive"))
      (node (ref "R13") (pin "2") (pinfunction "2_2") (pintype "passive"))
      (node (ref "R14") (pin "2") (pinfunction "2_2") (pintype "passive"))
    )
    (net (code "128") (name "Net-(Q6-B)") (class "Default")
      (node (ref "Q6") (pin "1") (pinfunction "B_1") (pintype "passive"))
      (node (ref "R10") (pin "2") (pinfunction "2_2") (pintype "passive"))
      (node (ref "R9") (pin "2") (pinfunction "2_2") (pintype "passive"))
    )
    (net (code "129") (name "Net-(Q6-E)") (class "Default")
      (node (ref "Q6") (pin "2") (pinfunction "E_2") (pintype "passive"))
      (node (ref "R15") (pin "2") (pinfunction "2_2") (pintype "passive"))
      (node (ref "R16") (pin "2") (pinfunction "2_2") (pintype "passive"))
      (node (ref "R20") (pin "2") (pinfunction "2_2") (pintype "passive"))
    )
    (net (code "130") (name "Net-(Q7-B)") (class "Default")
      (node (ref "Q7") (pin "1") (pinfunction "B_1") (pintype "passive"))
      (node (ref "R29") (pin "2") (pinfunction "2_2") (pintype "passive"))
      (node (ref "R30") (pin "2") (pinfunction "2_2") (pintype "passive"))
    )
    (net (code "131") (name "Net-(Q7-E)") (class "Default")
      (node (ref "Q7") (pin "2") (pinfunction "E_2") (pintype "passive"))
      (node (ref "R31") (pin "2") (pinfunction "2_2") (pintype "passive"))
      (node (ref "R32") (pin "2") (pinfunction "2_2") (pintype "passive"))
      (node (ref "R33") (pin "2") (pinfunction "2_2") (pintype "passive"))
    )
    (net (code "132") (name "Net-(Q8-B)") (class "Default")
      (node (ref "Q8") (pin "1") (pinfunction "B_1") (pintype "passive"))
      (node (ref "R24") (pin "2") (pinfunction "2_2") (pintype "passive"))
      (node (ref "R25") (pin "2") (pinfunction "2_2") (pintype "passive"))
    )
    (net (code "133") (name "Net-(Q8-E)") (class "Default")
      (node (ref "Q8") (pin "2") (pinfunction "E_2") (pintype "passive"))
      (node (ref "R26") (pin "2") (pinfunction "2_2") (pintype "passive"))
      (node (ref "R27") (pin "2") (pinfunction "2_2") (pintype "passive"))
      (node (ref "R28") (pin "2") (pinfunction "2_2") (pintype "passive"))
    )
    (net (code "134") (name "Net-(R18-Pad2)") (class "Default")
      (node (ref "R18") (pin "2") (pinfunction "2_2") (pintype "passive"))
      (node (ref "R22") (pin "2") (pinfunction "2_2") (pintype "passive"))
    )
    (net (code "135") (name "Net-(R53-Pad1)") (class "Default")
      (node (ref "R53") (pin "1") (pinfunction "1_1") (pintype "passive"))
      (node (ref "X6") (pin "2") (pinfunction "2_2") (pintype "passive"))
    )
    (net (code "136") (name "Net-(R54-Pad1)") (class "Default")
      (node (ref "R54") (pin "1") (pinfunction "1_1") (pintype "passive"))
      (node (ref "X6") (pin "3") (pinfunction "3_3") (pintype "passive"))
    )
    (net (code "137") (name "Net-(T2-B)") (class "Default")
      (node (ref "C2") (pin "2") (pinfunction "2_2") (pintype "passive"))
      (node (ref "R18") (pin "1") (pinfunction "1_1") (pintype "passive"))
      (node (ref "R19") (pin "2") (pinfunction "2_2") (pintype "passive"))
      (node (ref "T2") (pin "1") (pinfunction "B_1") (pintype "passive"))
    )
    (net (code "138") (name "Net-(U$6-A0)") (class "Default")
      (node (ref "U$6") (pin "P20") (pinfunction "A0_P20") (pintype "bidirectional"))
      (node (ref "U1") (pin "P24") (pinfunction "IO_L24N_6VREF_6_P24") (pintype "bidirectional"))
    )
    (net (code "139") (name "Net-(U$6-A1)") (class "Default")
      (node (ref "U$6") (pin "P19") (pinfunction "A1_P19") (pintype "bidirectional"))
      (node (ref "U1") (pin "P23") (pinfunction "IO_L24P_6_P23") (pintype "bidirectional"))
    )
    (net (code "140") (name "Net-(U$6-A2)") (class "Default")
      (node (ref "U$6") (pin "P18") (pinfunction "A2_P18") (pintype "bidirectional"))
      (node (ref "U1") (pin "P21") (pinfunction "IO_L40N_6_P21") (pintype "bidirectional"))
    )
    (net (code "141") (name "Net-(U$6-A3)") (class "Default")
      (node (ref "U$6") (pin "P17") (pinfunction "A3_P17") (pintype "bidirectional"))
      (node (ref "U1") (pin "P20") (pinfunction "IO_L40P_6VREF_6_P20") (pintype "bidirectional"))
    )
    (net (code "142") (name "Net-(U$6-A4)") (class "Default")
      (node (ref "U$6") (pin "P16") (pinfunction "A4_P16") (pintype "bidirectional"))
      (node (ref "U1") (pin "P18") (pinfunction "IO_L40N_7VREF_7_P18") (pintype "bidirectional"))
    )
    (net (code "143") (name "Net-(U$6-A5)") (class "Default")
      (node (ref "U$6") (pin "P15") (pinfunction "A5_P15") (pintype "bidirectional"))
      (node (ref "U1") (pin "P17") (pinfunction "IO_L40P_7_P17") (pintype "bidirectional"))
    )
    (net (code "144") (name "Net-(U$6-A6)") (class "Default")
      (node (ref "U$6") (pin "P14") (pinfunction "A6_P14") (pintype "bidirectional"))
      (node (ref "U1") (pin "P15") (pinfunction "IO_L24N_7_P15") (pintype "bidirectional"))
    )
    (net (code "145") (name "Net-(U$6-A7)") (class "Default")
      (node (ref "U$6") (pin "P13") (pinfunction "A7_P13") (pintype "bidirectional"))
      (node (ref "U1") (pin "P14") (pinfunction "IO_L24P_7_P14") (pintype "bidirectional"))
    )
    (net (code "146") (name "Net-(U$6-A8)") (class "Default")
      (node (ref "U$6") (pin "P3") (pinfunction "A8_P3") (pintype "bidirectional"))
      (node (ref "U1") (pin "P4") (pinfunction "IOVREF_7_P4") (pintype "bidirectional"))
    )
    (net (code "147") (name "Net-(U$6-A9)") (class "Default")
      (node (ref "U$6") (pin "P2") (pinfunction "A9_P2") (pintype "bidirectional"))
      (node (ref "U1") (pin "P2") (pinfunction "IO_L01N_7VRP_7_P2") (pintype "bidirectional"))
    )
    (net (code "148") (name "Net-(U$6-A10)") (class "Default")
      (node (ref "U$6") (pin "P31") (pinfunction "A10_P31") (pintype "bidirectional"))
      (node (ref "U1") (pin "P35") (pinfunction "IO_L01P_6VRN_6_P35") (pintype "bidirectional"))
    )
    (net (code "149") (name "Net-(U$6-A11)") (class "Default")
      (node (ref "U$6") (pin "P1") (pinfunction "A11_P1") (pintype "bidirectional"))
      (node (ref "U1") (pin "P1") (pinfunction "IO_L01P_7VRN_7_P1") (pintype "bidirectional"))
    )
    (net (code "150") (name "Net-(U$6-A12)") (class "Default")
      (node (ref "U$6") (pin "P12") (pinfunction "A12_P12") (pintype "bidirectional"))
      (node (ref "U1") (pin "P13") (pinfunction "IO_L23N_7_P13") (pintype "bidirectional"))
    )
    (net (code "151") (name "Net-(U$6-A13)") (class "Default")
      (node (ref "U$6") (pin "P4") (pinfunction "A13_P4") (pintype "bidirectional"))
      (node (ref "U1") (pin "P5") (pinfunction "IO_L20P_7_P5") (pintype "bidirectional"))
    )
    (net (code "152") (name "Net-(U$6-A14)") (class "Default")
      (node (ref "U$6") (pin "P11") (pinfunction "A14_P11") (pintype "bidirectional"))
      (node (ref "U1") (pin "P12") (pinfunction "IO_L23P_7_P12") (pintype "bidirectional"))
    )
    (net (code "153") (name "Net-(U$6-A15)") (class "Default")
      (node (ref "U$6") (pin "P7") (pinfunction "A15_P7") (pintype "bidirectional"))
      (node (ref "U1") (pin "P8") (pinfunction "IO_L21N_7_P8") (pintype "bidirectional"))
    )
    (net (code "154") (name "Net-(U$6-A16)") (class "Default")
      (node (ref "U$6") (pin "P10") (pinfunction "A16_P10") (pintype "bidirectional"))
      (node (ref "U1") (pin "P11") (pinfunction "IO_L22N_7_P11") (pintype "bidirectional"))
    )
    (net (code "155") (name "Net-(U$6-A17)") (class "Default")
      (node (ref "U$6") (pin "P6") (pinfunction "A17_P6") (pintype "bidirectional"))
      (node (ref "U1") (pin "P7") (pinfunction "IO_L21P_7_P7") (pintype "bidirectional"))
    )
    (net (code "156") (name "Net-(U$6-A18)") (class "Default")
      (node (ref "U$6") (pin "P9") (pinfunction "A18_P9") (pintype "bidirectional"))
      (node (ref "U1") (pin "P10") (pinfunction "IO_L22P_7_P10") (pintype "bidirectional"))
    )
    (net (code "157") (name "Net-(U$6-DQ0)") (class "Default")
      (node (ref "U$6") (pin "P21") (pinfunction "DQ0_P21") (pintype "bidirectional"))
      (node (ref "U1") (pin "P25") (pinfunction "IO_L23P_6_P25") (pintype "bidirectional"))
    )
    (net (code "158") (name "Net-(U$6-DQ1)") (class "Default")
      (node (ref "U$6") (pin "P22") (pinfunction "DQ1_P22") (pintype "bidirectional"))
      (node (ref "U1") (pin "P26") (pinfunction "IO_L23N_6_P26") (pintype "bidirectional"))
    )
    (net (code "159") (name "Net-(U$6-DQ2)") (class "Default")
      (node (ref "U$6") (pin "P23") (pinfunction "DQ2_P23") (pintype "bidirectional"))
      (node (ref "U1") (pin "P27") (pinfunction "IO_L22P_6_P27") (pintype "bidirectional"))
    )
    (net (code "160") (name "Net-(U$6-DQ3)") (class "Default")
      (node (ref "U$6") (pin "P25") (pinfunction "DQ3_P25") (pintype "bidirectional"))
      (node (ref "U1") (pin "P28") (pinfunction "IO_L22N_6_P28") (pintype "bidirectional"))
    )
    (net (code "161") (name "Net-(U$6-DQ4)") (class "Default")
      (node (ref "U$6") (pin "P26") (pinfunction "DQ4_P26") (pintype "bidirectional"))
      (node (ref "U1") (pin "P30") (pinfunction "IO_L21P_6_P30") (pintype "bidirectional"))
    )
    (net (code "162") (name "Net-(U$6-DQ5)") (class "Default")
      (node (ref "U$6") (pin "P27") (pinfunction "DQ5_P27") (pintype "bidirectional"))
      (node (ref "U1") (pin "P31") (pinfunction "IO_L21N_6_P31") (pintype "bidirectional"))
    )
    (net (code "163") (name "Net-(U$6-DQ6)") (class "Default")
      (node (ref "U$6") (pin "P28") (pinfunction "DQ6_P28") (pintype "bidirectional"))
      (node (ref "U1") (pin "P32") (pinfunction "IO_L20P_6_P32") (pintype "bidirectional"))
    )
    (net (code "164") (name "Net-(U$6-DQ7)") (class "Default")
      (node (ref "U$6") (pin "P29") (pinfunction "DQ7_P29") (pintype "bidirectional"))
      (node (ref "U1") (pin "P33") (pinfunction "IO_L20N_6_P33") (pintype "bidirectional"))
    )
    (net (code "165") (name "Net-(U$6-OE)") (class "Default")
      (node (ref "U$6") (pin "P32") (pinfunction "OE_P32") (pintype "bidirectional"))
      (node (ref "U1") (pin "P36") (pinfunction "IO_L01N_6VRP_6_P36") (pintype "bidirectional"))
    )
    (net (code "166") (name "Net-(U$6-WE)") (class "Default")
      (node (ref "U$6") (pin "P5") (pinfunction "WE_P5") (pintype "bidirectional"))
      (node (ref "U1") (pin "P6") (pinfunction "IO_L20N_7_P6") (pintype "bidirectional"))
    )
    (net (code "167") (name "Net-(U1A-IO_L27N_0)") (class "Default")
      (node (ref "SV3") (pin "3") (pinfunction "3_3") (pintype "passive"))
      (node (ref "U1") (pin "P137") (pinfunction "IO_L27N_0_P137") (pintype "bidirectional"))
    )
    (net (code "168") (name "Net-(U1A-IO_L27P_0)") (class "Default")
      (node (ref "SV3") (pin "4") (pinfunction "4_4") (pintype "passive"))
      (node (ref "U1") (pin "P135") (pinfunction "IO_L27P_0_P135") (pintype "bidirectional"))
    )
    (net (code "169") (name "Net-(U1A-IO_L30N_0)") (class "Default")
      (node (ref "SV3") (pin "5") (pinfunction "5_5") (pintype "passive"))
      (node (ref "U1") (pin "P132") (pinfunction "IO_L30N_0_P132") (pintype "bidirectional"))
    )
    (net (code "170") (name "Net-(U1A-IO_L31N_0)") (class "Default")
      (node (ref "SV3") (pin "6") (pinfunction "6_6") (pintype "passive"))
      (node (ref "U1") (pin "P130") (pinfunction "IO_L31N_0_P130") (pintype "bidirectional"))
    )
    (net (code "171") (name "Net-(U1A-IO_L31P_0VREF_0)") (class "Default")
      (node (ref "SV3") (pin "7") (pinfunction "7_7") (pintype "passive"))
      (node (ref "U1") (pin "P129") (pinfunction "IO_L31P_0VREF_0_P129") (pintype "bidirectional"))
    )
    (net (code "172") (name "Net-(U1A-IO_L32N_0GCLK7)") (class "Default")
      (node (ref "SV3") (pin "8") (pinfunction "8_8") (pintype "passive"))
      (node (ref "U1") (pin "P128") (pinfunction "IO_L32N_0GCLK7_P128") (pintype "bidirectional"))
    )
    (net (code "173") (name "Net-(U1A-IO_L32P_0GCLK6)") (class "Default")
      (node (ref "SV3") (pin "9") (pinfunction "9_9") (pintype "passive"))
      (node (ref "U1") (pin "P127") (pinfunction "IO_L32P_0GCLK6_P127") (pintype "bidirectional"))
    )
    (net (code "174") (name "Net-(U1C-IO_L31N_1VREF_1)") (class "Default")
      (node (ref "SV3") (pin "10") (pinfunction "10_10") (pintype "passive"))
      (node (ref "U1") (pin "P123") (pinfunction "IO_L31N_1VREF_1_P123") (pintype "bidirectional"))
    )
    (net (code "175") (name "Net-(U1N-TCK)") (class "Default")
      (node (ref "R2") (pin "1") (pinfunction "1_1") (pintype "passive"))
      (node (ref "U1") (pin "P110") (pinfunction "TCK_P110") (pintype "bidirectional"))
    )
    (net (code "176") (name "Net-(U1N-TDI)") (class "Default")
      (node (ref "R1") (pin "1") (pinfunction "1_1") (pintype "passive"))
      (node (ref "U1") (pin "P144") (pinfunction "TDI_P144") (pintype "bidirectional"))
    )
    (net (code "177") (name "Net-(U1N-TMS)") (class "Default")
      (node (ref "R3") (pin "1") (pinfunction "1_1") (pintype "passive"))
      (node (ref "U1") (pin "P111") (pinfunction "TMS_P111") (pintype "bidirectional"))
    )
    (net (code "178") (name "unconnected-(IC1-NC.1-Pad2)") (class "Default")
      (node (ref "IC1") (pin "2") (pinfunction "NC.1_2") (pintype "bidirectional"))
    )
    (net (code "179") (name "unconnected-(IC1-NC.2-Pad9)") (class "Default")
      (node (ref "IC1") (pin "9") (pinfunction "NC.2_9") (pintype "bidirectional"))
    )
    (net (code "180") (name "unconnected-(IC1-NC.3-Pad12)") (class "Default")
      (node (ref "IC1") (pin "12") (pinfunction "NC.3_12") (pintype "bidirectional"))
    )
    (net (code "181") (name "unconnected-(IC1-NC.4-Pad14)") (class "Default")
      (node (ref "IC1") (pin "14") (pinfunction "NC.4_14") (pintype "bidirectional"))
    )
    (net (code "182") (name "unconnected-(IC1-NC.5-Pad15)") (class "Default")
      (node (ref "IC1") (pin "15") (pinfunction "NC.5_15") (pintype "bidirectional"))
    )
    (net (code "183") (name "unconnected-(IC1-NC.6-Pad16)") (class "Default")
      (node (ref "IC1") (pin "16") (pinfunction "NC.6_16") (pintype "bidirectional"))
    )
    (net (code "184") (name "unconnected-(IC1-{slash}CEO-Pad13)") (class "Default")
      (node (ref "IC1") (pin "13") (pinfunction "/CEO_13") (pintype "bidirectional"))
    )
    (net (code "185") (name "unconnected-(JP1-Pad3)") (class "Default")
      (node (ref "JP1") (pin "3") (pinfunction "3_3") (pintype "passive"))
    )
    (net (code "186") (name "unconnected-(JP1-Pad4)") (class "Default")
      (node (ref "JP1") (pin "4") (pinfunction "4_4") (pintype "passive"))
    )
    (net (code "187") (name "unconnected-(JP1-Pad5)") (class "Default")
      (node (ref "JP1") (pin "5") (pinfunction "5_5") (pintype "passive"))
    )
    (net (code "188") (name "unconnected-(JP1-Pad6)") (class "Default")
      (node (ref "JP1") (pin "6") (pinfunction "6_6") (pintype "passive"))
    )
    (net (code "189") (name "unconnected-(JP1-Pad7)") (class "Default")
      (node (ref "JP1") (pin "7") (pinfunction "7_7") (pintype "passive"))
    )
    (net (code "190") (name "unconnected-(JP1-Pad8)") (class "Default")
      (node (ref "JP1") (pin "8") (pinfunction "8_8") (pintype "passive"))
    )
    (net (code "191") (name "unconnected-(JP1-Pad9)") (class "Default")
      (node (ref "JP1") (pin "9") (pinfunction "9_9") (pintype "passive"))
    )
    (net (code "192") (name "unconnected-(JP1-Pad10)") (class "Default")
      (node (ref "JP1") (pin "10") (pinfunction "10_10") (pintype "passive"))
    )
    (net (code "193") (name "unconnected-(JP1-Pad11)") (class "Default")
      (node (ref "JP1") (pin "11") (pinfunction "11_11") (pintype "passive"))
    )
    (net (code "194") (name "unconnected-(JP1-Pad12)") (class "Default")
      (node (ref "JP1") (pin "12") (pinfunction "12_12") (pintype "passive"))
    )
    (net (code "195") (name "unconnected-(JP1-Pad13)") (class "Default")
      (node (ref "JP1") (pin "13") (pinfunction "13_13") (pintype "passive"))
    )
    (net (code "196") (name "unconnected-(JP1-Pad14)") (class "Default")
      (node (ref "JP1") (pin "14") (pinfunction "14_14") (pintype "passive"))
    )
    (net (code "197") (name "unconnected-(JP1-Pad15)") (class "Default")
      (node (ref "JP1") (pin "15") (pinfunction "15_15") (pintype "passive"))
    )
    (net (code "198") (name "unconnected-(JP1-Pad16)") (class "Default")
      (node (ref "JP1") (pin "16") (pinfunction "16_16") (pintype "passive"))
    )
    (net (code "199") (name "unconnected-(JP1-Pad17)") (class "Default")
      (node (ref "JP1") (pin "17") (pinfunction "17_17") (pintype "passive"))
    )
    (net (code "200") (name "unconnected-(JP1-Pad18)") (class "Default")
      (node (ref "JP1") (pin "18") (pinfunction "18_18") (pintype "passive"))
    )
    (net (code "201") (name "unconnected-(JP1-Pad19)") (class "Default")
      (node (ref "JP1") (pin "19") (pinfunction "19_19") (pintype "passive"))
    )
    (net (code "202") (name "unconnected-(JP1-Pad20)") (class "Default")
      (node (ref "JP1") (pin "20") (pinfunction "20_20") (pintype "passive"))
    )
    (net (code "203") (name "unconnected-(REG1.2-VOUT2-Pad2)") (class "Default")
      (node (ref "REG1.2") (pin "2") (pinfunction "VOUT2_2") (pintype "bidirectional"))
    )
    (net (code "204") (name "unconnected-(REG2.5-VOUT2-Pad2)") (class "Default")
      (node (ref "REG2.5") (pin "2") (pinfunction "VOUT2_2") (pintype "bidirectional"))
    )
    (net (code "205") (name "unconnected-(U$2-TRI-PadENA)") (class "Default")
      (node (ref "U$2") (pin "ENA") (pinfunction "TRI_ENA") (pintype "input"))
    )
    (net (code "206") (name "unconnected-(U$3-CARD_DETECT-PadCD)") (class "Default")
      (node (ref "U$3") (pin "CD") (pinfunction "CARD_DETECT_CD") (pintype "passive"))
    )
    (net (code "207") (name "unconnected-(U$3-DAT1-Pad8)") (class "Default")
      (node (ref "U$3") (pin "8") (pinfunction "DAT1_8") (pintype "bidirectional"))
    )
    (net (code "208") (name "unconnected-(U$3-DAT2-Pad9)") (class "Default")
      (node (ref "U$3") (pin "9") (pinfunction "DAT2_9") (pintype "bidirectional"))
    )
    (net (code "209") (name "unconnected-(U$3-WRITE_PROTECT-PadWP)") (class "Default")
      (node (ref "U$3") (pin "WP") (pinfunction "WRITE_PROTECT_WP") (pintype "passive"))
    )
    (net (code "210") (name "unconnected-(U$4-VOUT2-Pad2)") (class "Default")
      (node (ref "U$4") (pin "2") (pinfunction "VOUT2_2") (pintype "bidirectional"))
    )
    (net (code "211") (name "unconnected-(U1N-HSWAP_EN-PadP142)") (class "Default")
      (node (ref "U1") (pin "P142") (pinfunction "HSWAP_EN_P142") (pintype "bidirectional"))
    )
    (net (code "212") (name "unconnected-(X1-Pad10)") (class "Default")
      (node (ref "X1") (pin "10") (pinfunction "10_10") (pintype "passive"))
    )
    (net (code "213") (name "unconnected-(X1-Pad12)") (class "Default")
      (node (ref "X1") (pin "12") (pinfunction "12_12") (pintype "passive"))
    )
    (net (code "214") (name "unconnected-(X3-Pad2)") (class "Default")
      (node (ref "X3") (pin "2") (pinfunction "2_2") (pintype "passive"))
    )
    (net (code "215") (name "unconnected-(X3-Pad8)") (class "Default")
      (node (ref "X3") (pin "8") (pinfunction "8_8") (pintype "passive"))
    )
    (net (code "216") (name "unconnected-(X4-PadG2)") (class "Default")
      (node (ref "X4") (pin "G2") (pinfunction "G2_G2") (pintype "passive"))
    )
    (net (code "217") (name "unconnected-(X5-PadG2)") (class "Default")
      (node (ref "X5") (pin "G2") (pinfunction "G2_G2") (pintype "passive"))
    )
    (net (code "218") (name "unconnected-(X6-Pad1)") (class "Default")
      (node (ref "X6") (pin "1") (pinfunction "1_1") (pintype "passive"))
    )
  )
)
